# Dashboard_rev4.net
KiCad netlist of a schematic drawn in EAGLE
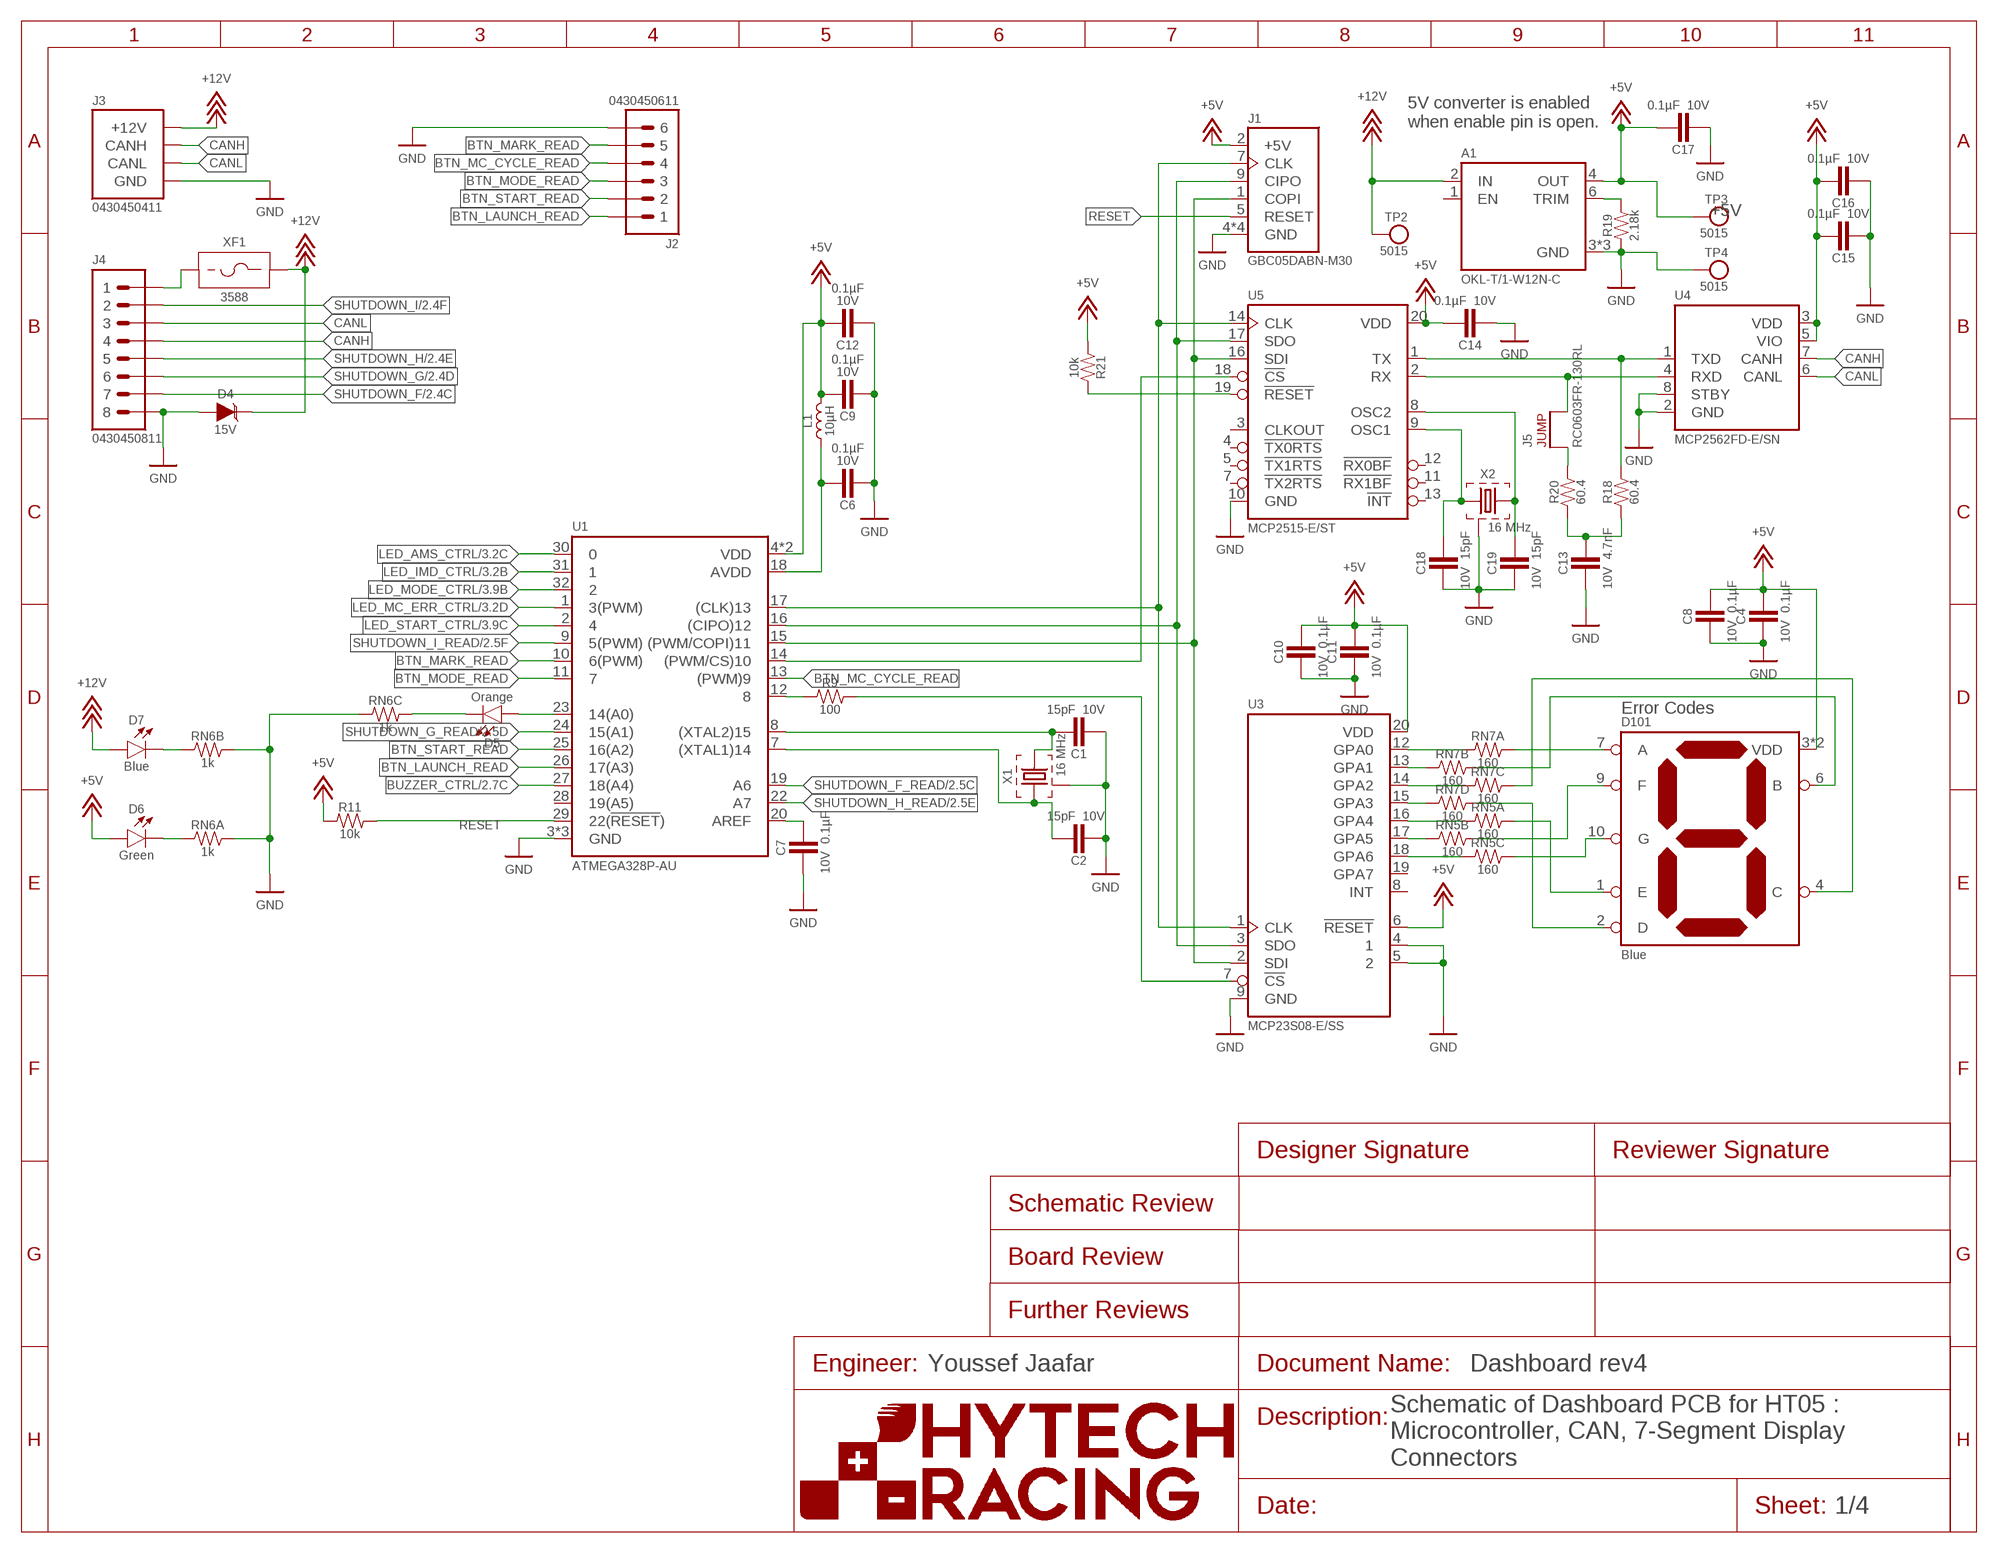
[diagram p0: schematic, sheet 1]
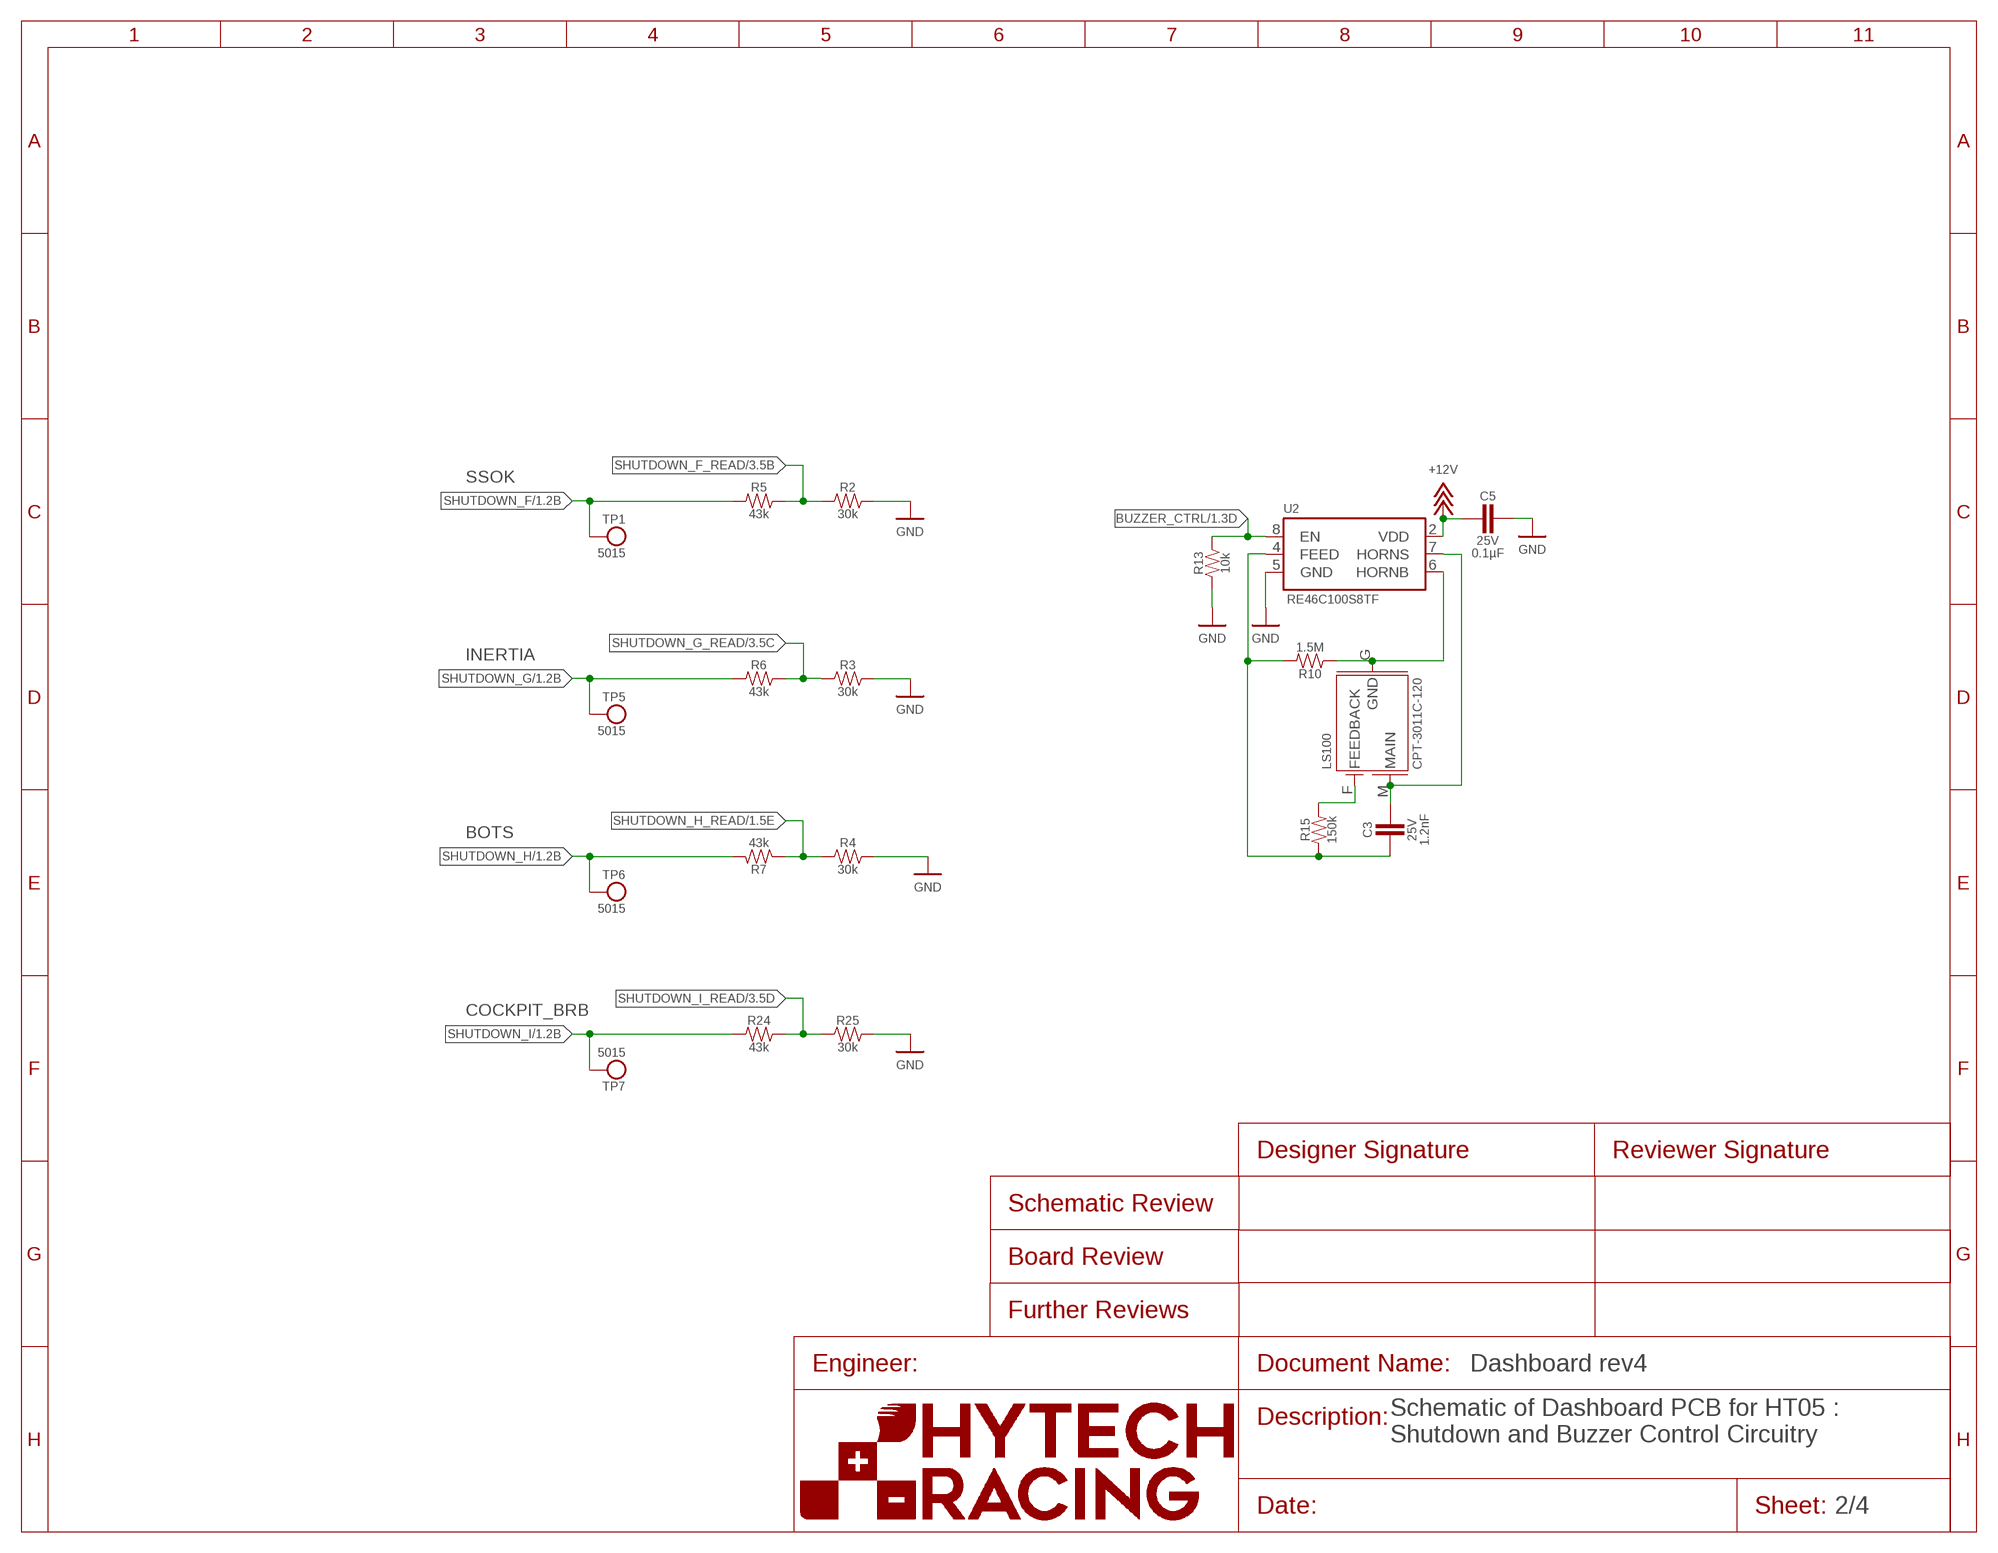
[diagram p1: schematic, sheet 2]
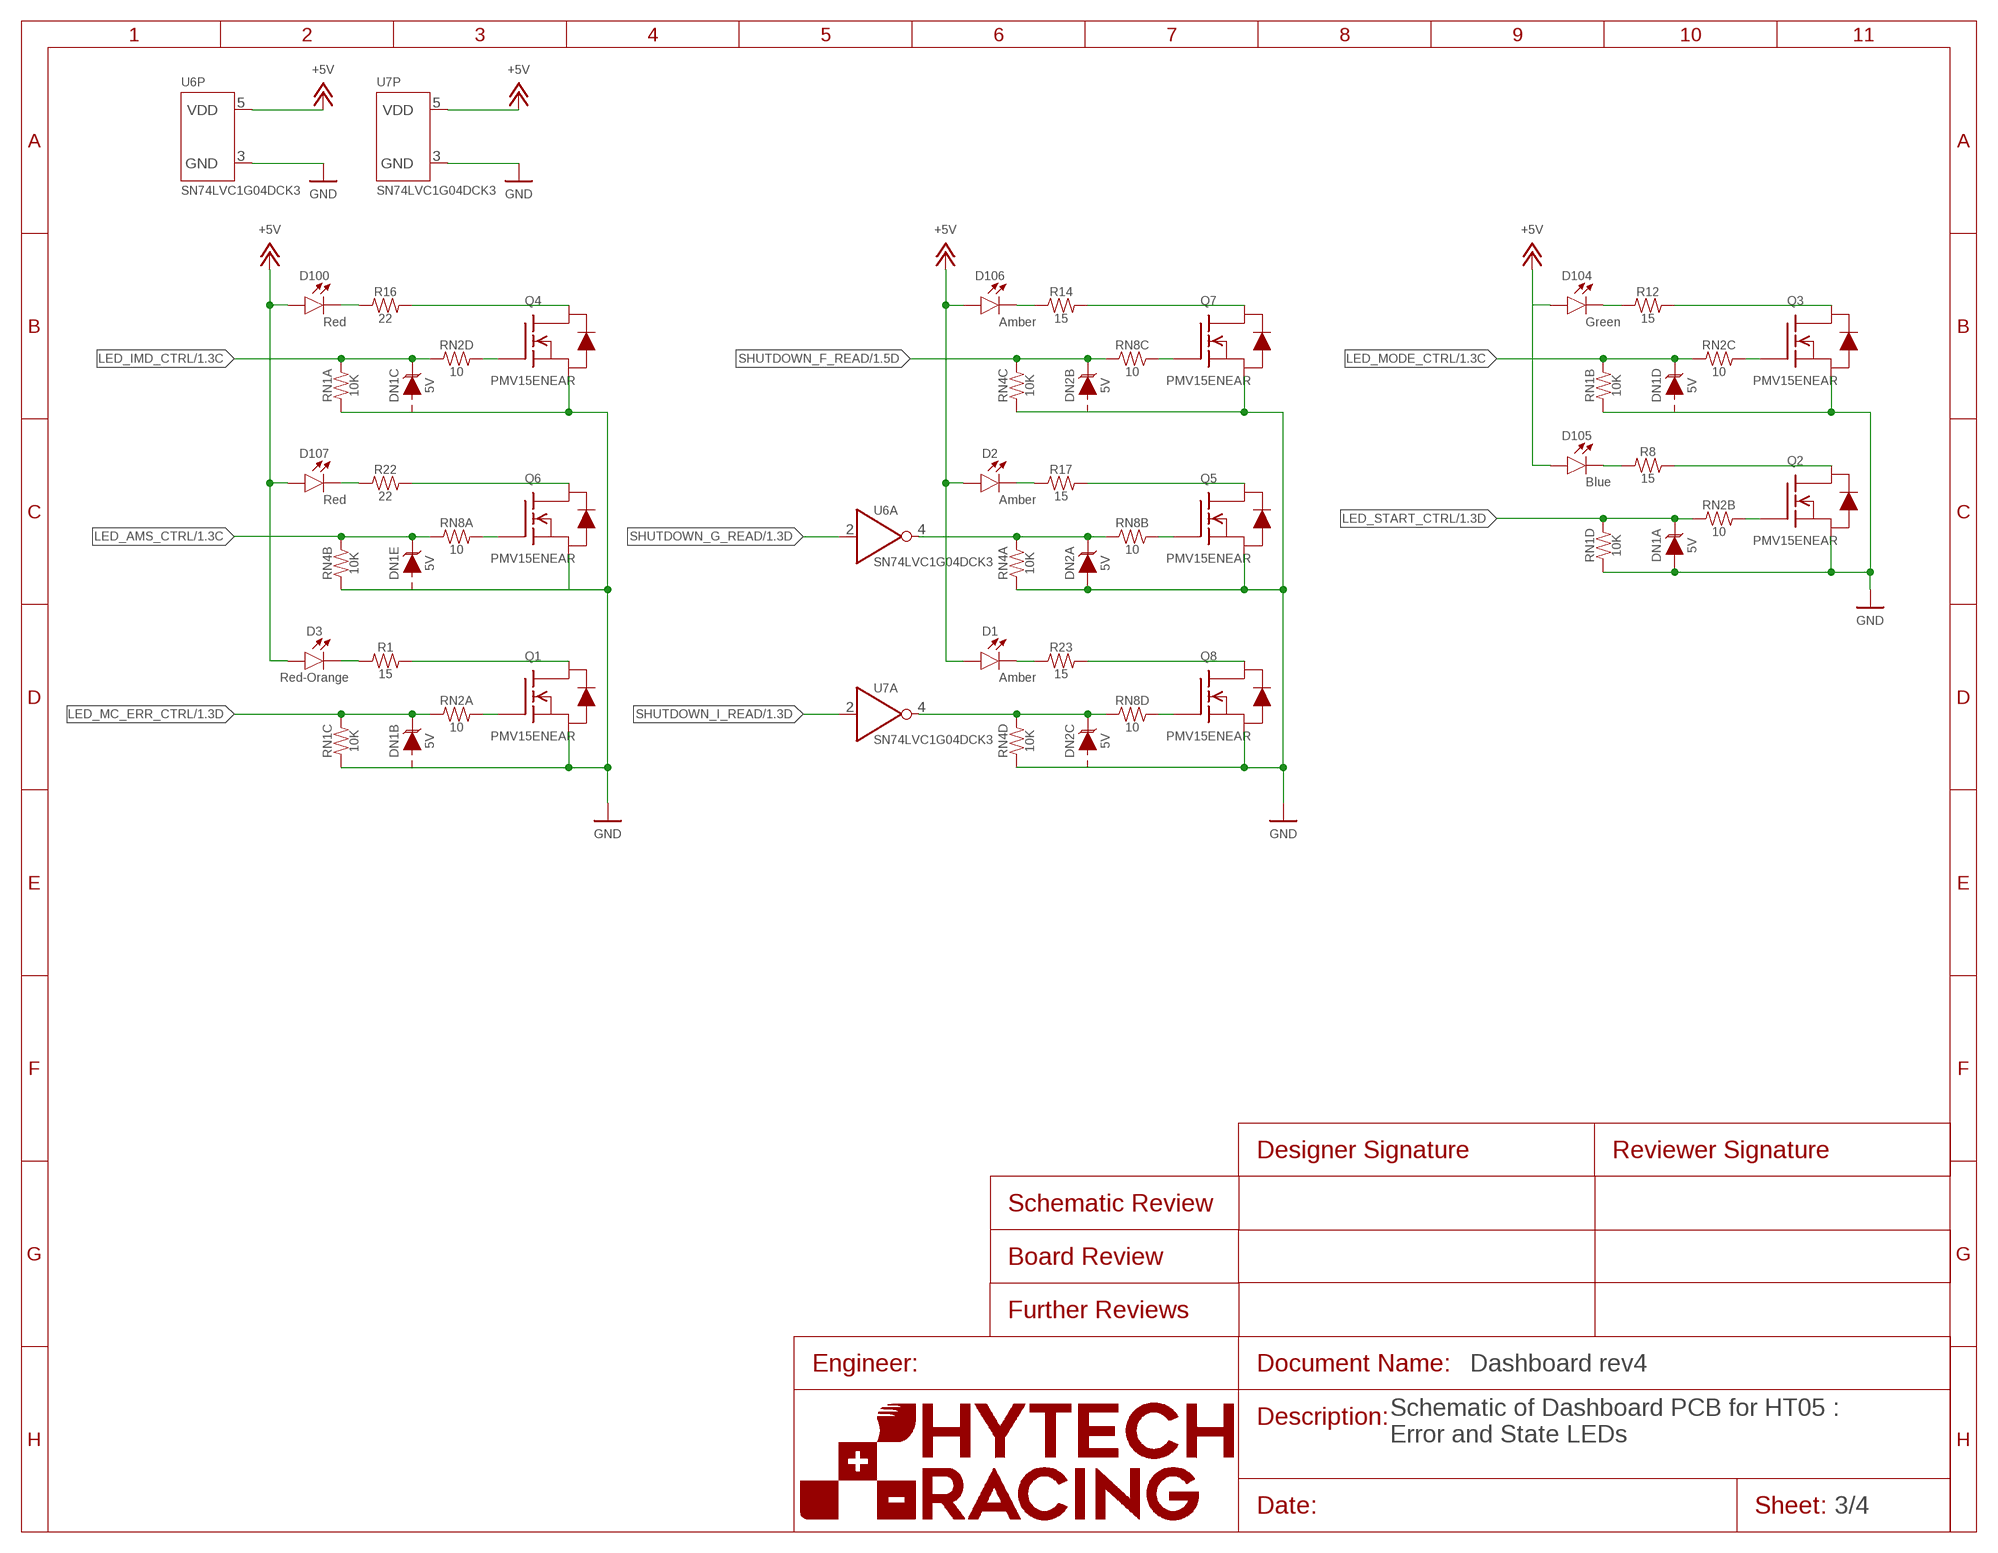
[diagram p2: schematic, sheet 3]
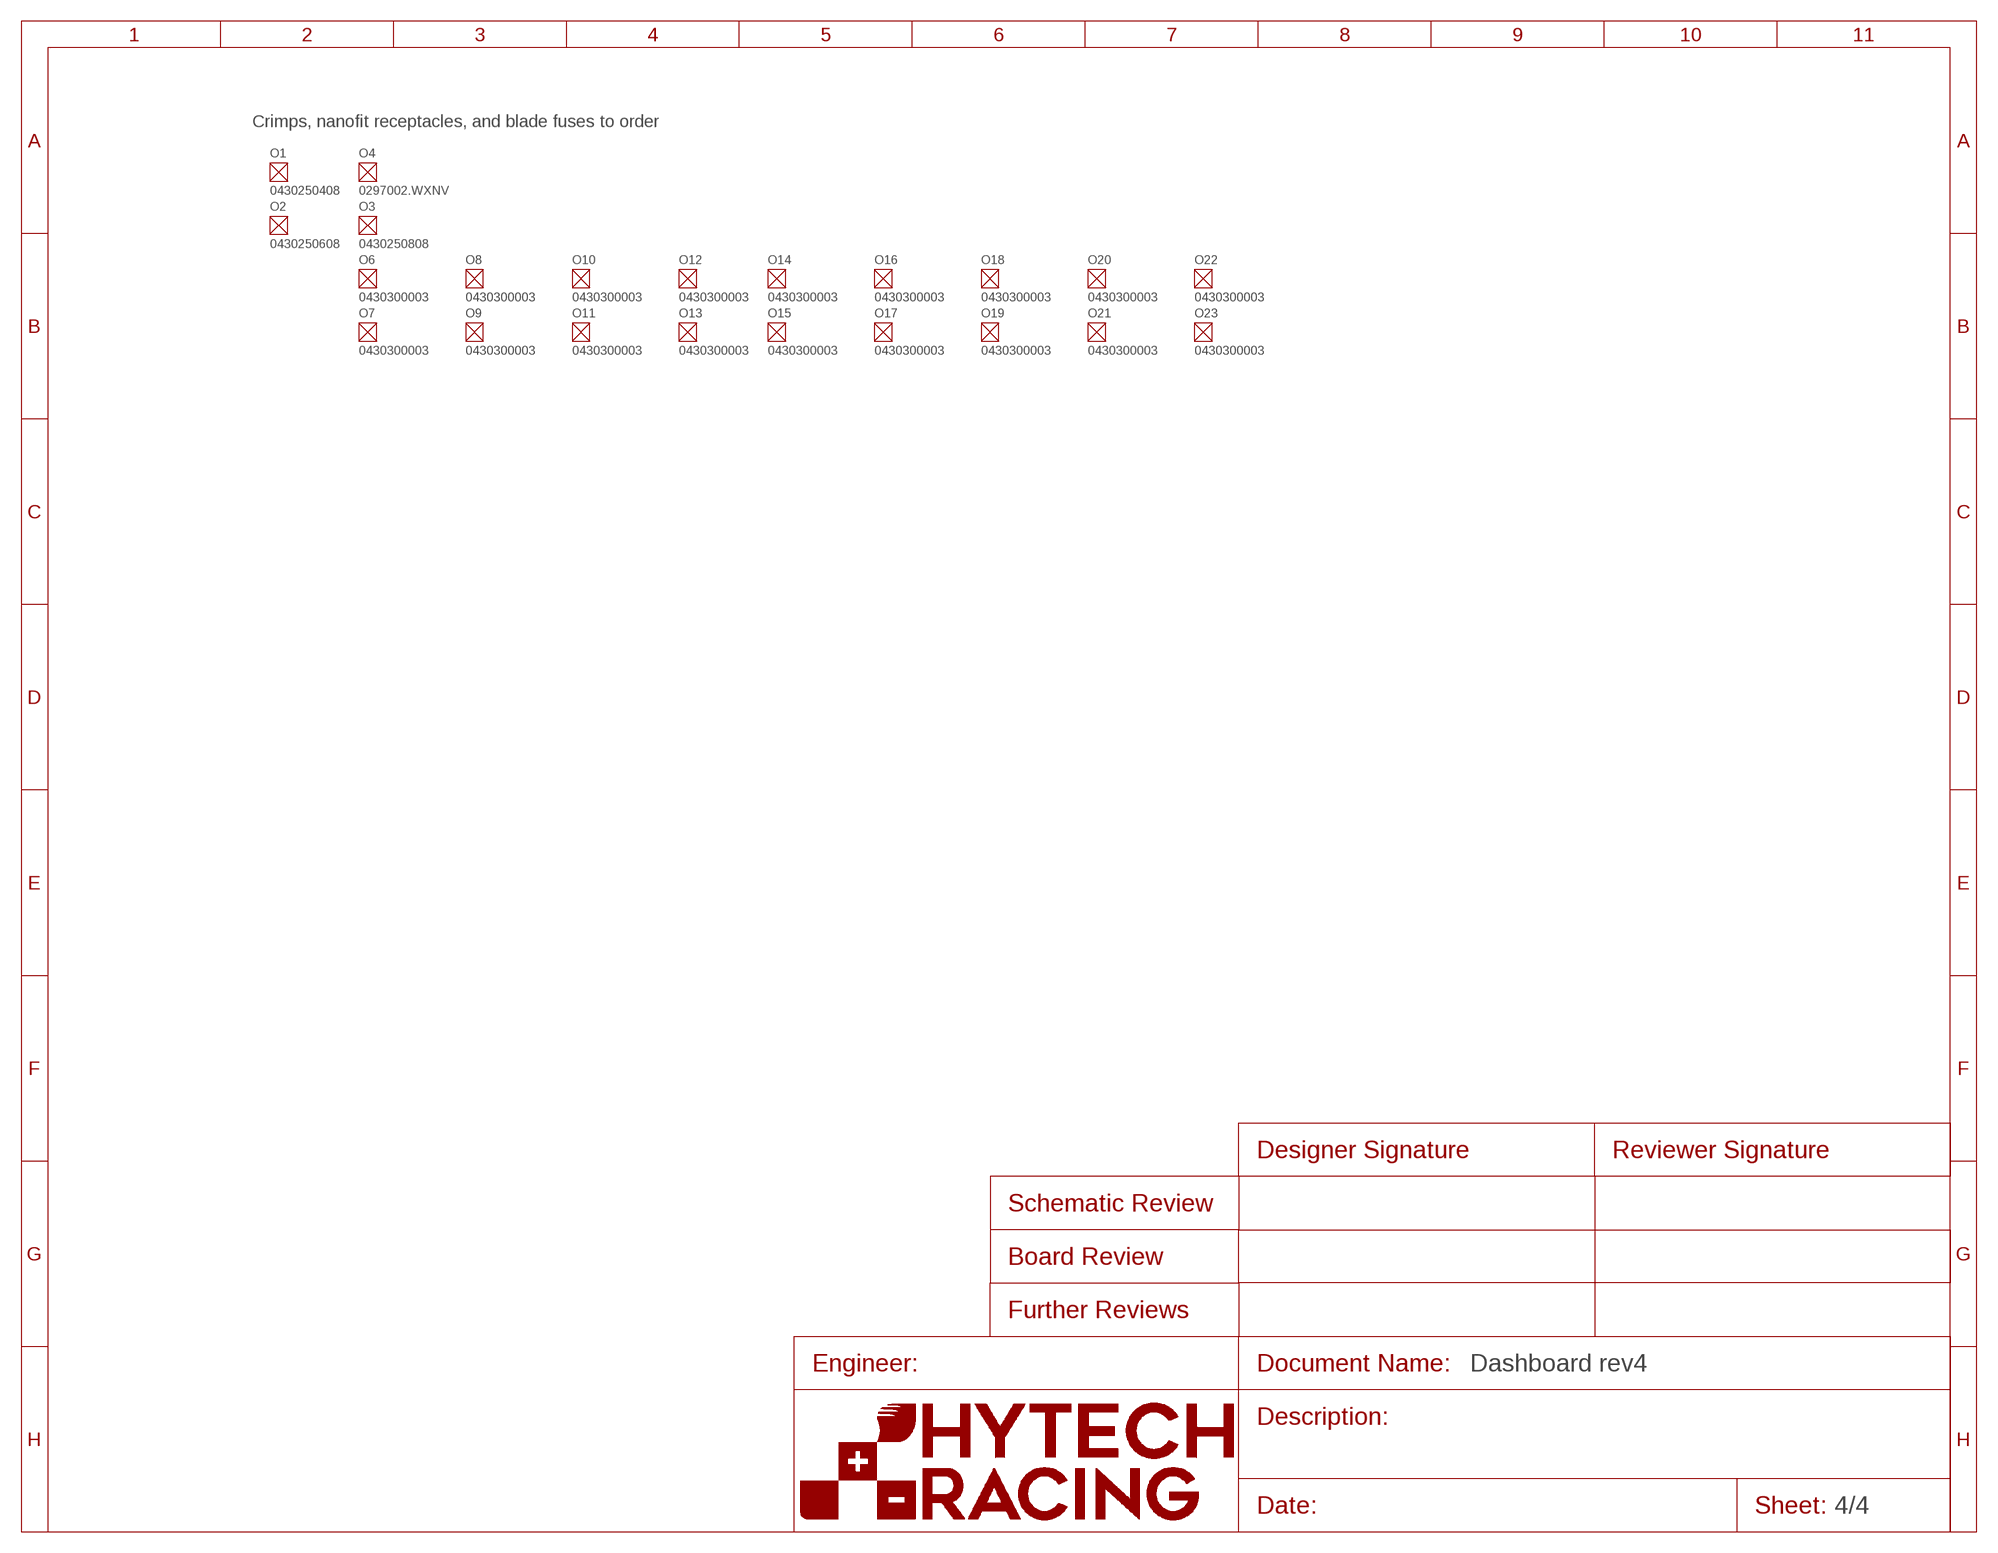
[diagram p3: schematic, sheet 4]

(export (version "E")
  (design (tool "Eeschema 10.0.6"))
  (components
    (comp (ref "C3")
      (value "CAPACITOR_0603_25V_1.2NF")
      (footprint "eagle-import:0603-CAP")
      (fields
        (field (name "CAPACITANCE") "1.2nF")
        (field (name "MANUFACTURER") "YAGEO")
        (field (name "MPN") "CC0603KRX7R8BB122")
        (field (name "TOLERANCE") "10%")
        (field (name "VOLTAGE") "25V")
      )
      (libsource (lib "eagle-import") (part "CAPACITOR_?_060325V_1.2NF"))
    )
    (comp (ref "C5")
      (value "CAPACITOR_0603_25V_0.1UF")
      (footprint "eagle-import:0603-CAP")
      (fields
        (field (name "CAPACITANCE") "0.1µF")
        (field (name "MANUFACTURER") "Samsung Electro-Mechanics")
        (field (name "MPN") "CL10B104KA8NNNC")
        (field (name "TOLERANCE") "10%")
        (field (name "VOLTAGE") "25V")
      )
      (libsource (lib "eagle-import") (part "CAPACITOR_?_060325V_0.1UF"))
    )
    (comp (ref "LS100")
      (value "BUZZER_3_PIN_CPT-3011C-120")
      (footprint "eagle-import:CPT-3011C-120")
      (fields
        (field (name "MANUFACTURER") "CUI Devices")
        (field (name "MPN") "CPT-3011C-120")
        (field (name "VOLTAGE") "12V")
      )
      (libsource (lib "eagle-import") (part "BUZZER_3_PIN_CPT-3011C-120"))
    )
    (comp (ref "R2")
      (value "RESISTOR_0603_30K")
      (footprint "eagle-import:0603-RES")
      (fields
        (field (name "MANUFACTURER") "Panasonic Electronic Components")
        (field (name "MPN") "ERA-3ARB303V")
        (field (name "POWER") "0.1W")
        (field (name "RESISTANCE") "30k")
      )
      (libsource (lib "eagle-import") (part "RESISTOR_?_060330K"))
    )
    (comp (ref "R3")
      (value "RESISTOR_0603_30K")
      (footprint "eagle-import:0603-RES")
      (fields
        (field (name "MANUFACTURER") "Panasonic Electronic Components")
        (field (name "MPN") "ERA-3ARB303V")
        (field (name "POWER") "0.1W")
        (field (name "RESISTANCE") "30k")
      )
      (libsource (lib "eagle-import") (part "RESISTOR_?_060330K"))
    )
    (comp (ref "R4")
      (value "RESISTOR_0603_30K")
      (footprint "eagle-import:0603-RES")
      (fields
        (field (name "MANUFACTURER") "Panasonic Electronic Components")
        (field (name "MPN") "ERA-3ARB303V")
        (field (name "POWER") "0.1W")
        (field (name "RESISTANCE") "30k")
      )
      (libsource (lib "eagle-import") (part "RESISTOR_?_060330K"))
    )
    (comp (ref "R5")
      (value "RESISTOR_0603_43K")
      (footprint "eagle-import:0603-RES")
      (fields
        (field (name "MANUFACTURER") "Yageo")
        (field (name "MPN") "RC0603FR-0743KL")
        (field (name "POWER") "0.1W")
        (field (name "RESISTANCE") "43k")
      )
      (libsource (lib "eagle-import") (part "RESISTOR_?_060343K"))
    )
    (comp (ref "R6")
      (value "RESISTOR_0603_43K")
      (footprint "eagle-import:0603-RES")
      (fields
        (field (name "MANUFACTURER") "Yageo")
        (field (name "MPN") "RC0603FR-0743KL")
        (field (name "POWER") "0.1W")
        (field (name "RESISTANCE") "43k")
      )
      (libsource (lib "eagle-import") (part "RESISTOR_?_060343K"))
    )
    (comp (ref "R7")
      (value "RESISTOR_0603_43K")
      (footprint "eagle-import:0603-RES")
      (fields
        (field (name "MANUFACTURER") "Yageo")
        (field (name "MPN") "RC0603FR-0743KL")
        (field (name "POWER") "0.1W")
        (field (name "RESISTANCE") "43k")
      )
      (libsource (lib "eagle-import") (part "RESISTOR_?_060343K"))
    )
    (comp (ref "R10")
      (value "RESISTOR_0603_1.5M")
      (footprint "eagle-import:0603-RES")
      (fields
        (field (name "MANUFACTURER") "Yageo")
        (field (name "MPN") "RC0603FR-071M5L")
        (field (name "POWER") "0.1W")
        (field (name "RESISTANCE") "1.5M")
      )
      (libsource (lib "eagle-import") (part "RESISTOR_?_06031.5M"))
    )
    (comp (ref "R13")
      (value "RESISTOR_0603_10K")
      (footprint "eagle-import:0603-RES")
      (fields
        (field (name "MANUFACTURER") "Yageo")
        (field (name "MPN") "RC0603FR-0710KL")
        (field (name "POWER") "0.1W")
        (field (name "RESISTANCE") "10k")
      )
      (libsource (lib "eagle-import") (part "RESISTOR_?_060310K"))
    )
    (comp (ref "R15")
      (value "RESISTOR_0603_150K")
      (footprint "eagle-import:0603-RES")
      (fields
        (field (name "MANUFACTURER") "Panasonic Electronic Components")
        (field (name "MPN") "ERA-3AEB154V")
        (field (name "POWER") "0.1W")
        (field (name "RESISTANCE") "150k")
      )
      (libsource (lib "eagle-import") (part "RESISTOR_?_0603150K"))
    )
    (comp (ref "R24")
      (value "RESISTOR_0603_43K")
      (footprint "eagle-import:0603-RES")
      (fields
        (field (name "MANUFACTURER") "Yageo")
        (field (name "MPN") "RC0603FR-0743KL")
        (field (name "POWER") "0.1W")
        (field (name "RESISTANCE") "43k")
      )
      (libsource (lib "eagle-import") (part "RESISTOR_?_060343K"))
    )
    (comp (ref "R25")
      (value "RESISTOR_0603_30K")
      (footprint "eagle-import:0603-RES")
      (fields
        (field (name "MANUFACTURER") "Panasonic Electronic Components")
        (field (name "MPN") "ERA-3ARB303V")
        (field (name "POWER") "0.1W")
        (field (name "RESISTANCE") "30k")
      )
      (libsource (lib "eagle-import") (part "RESISTOR_?_060330K"))
    )
    (comp (ref "TP1")
      (value "TEST_POINT")
      (footprint "eagle-import:5015")
      (fields (field (name "MPN") "5015") (field (name "MANUFACTURER") "Keystone Electronics"))
      (libsource (lib "eagle-import") (part "TEST_POINT"))
    )
    (comp (ref "TP5")
      (value "TEST_POINT")
      (footprint "eagle-import:5015")
      (fields (field (name "MPN") "5015") (field (name "MANUFACTURER") "Keystone Electronics"))
      (libsource (lib "eagle-import") (part "TEST_POINT"))
    )
    (comp (ref "TP6")
      (value "TEST_POINT")
      (footprint "eagle-import:5015")
      (fields (field (name "MPN") "5015") (field (name "MANUFACTURER") "Keystone Electronics"))
      (libsource (lib "eagle-import") (part "TEST_POINT"))
    )
    (comp (ref "TP7")
      (value "TEST_POINT")
      (footprint "eagle-import:5015")
      (fields (field (name "MPN") "5015") (field (name "MANUFACTURER") "Keystone Electronics"))
      (libsource (lib "eagle-import") (part "TEST_POINT"))
    )
    (comp (ref "U2")
      (value "RE46C100")
      (footprint "eagle-import:SOIC-08(NARROW,0.15_)")
      (fields (field (name "MPN") " RE46C100S8TF") (field (name "MANUFACTURER") "Microchip Technology"))
      (libsource (lib "eagle-import") (part "RE46C100"))
    )
    (comp (ref "D1")
      (value "LED_2835_AMBER")
      (footprint "eagle-import:2835-LED")
      (fields
        (field (name "COLOR") "Amber")
        (field (name "MANUFACTURER") "Lumileds")
        (field (name "MPN") "L128-PCA1003500000")
      )
      (libsource (lib "eagle-import") (part "LED_?_2835AMBER"))
    )
    (comp (ref "D2")
      (value "LED_2835_AMBER")
      (footprint "eagle-import:2835-LED")
      (fields
        (field (name "COLOR") "Amber")
        (field (name "MANUFACTURER") "Lumileds")
        (field (name "MPN") "L128-PCA1003500000")
      )
      (libsource (lib "eagle-import") (part "LED_?_2835AMBER"))
    )
    (comp (ref "D3")
      (value "LED_2835_RED-ORANGE")
      (footprint "eagle-import:2835-LED")
      (fields
        (field (name "COLOR") "Red-Orange")
        (field (name "MANUFACTURER") "Lumileds")
        (field (name "MPN") "L128-RNG1003500000 ")
      )
      (libsource (lib "eagle-import") (part "LED_?_2835RED-ORANGE"))
    )
    (comp (ref "D100")
      (value "LED_2835_RED")
      (footprint "eagle-import:2835-LED")
      (fields
        (field (name "COLOR") "Red")
        (field (name "MANUFACTURER") "Lumileds")
        (field (name "MPN") "L128-RED1003500000")
      )
      (libsource (lib "eagle-import") (part "LED_?_2835RED"))
    )
    (comp (ref "D104")
      (value "LED_2835_GREEN")
      (footprint "eagle-import:2835-LED")
      (fields
        (field (name "COLOR") "Green")
        (field (name "MANUFACTURER") "Lumileds")
        (field (name "MPN") "L128-GRN1003500000")
      )
      (libsource (lib "eagle-import") (part "LED_?_2835GREEN"))
    )
    (comp (ref "D105")
      (value "LED_2835_BLUE")
      (footprint "eagle-import:2835-LED")
      (fields
        (field (name "COLOR") "Blue")
        (field (name "MANUFACTURER") "Lumileds")
        (field (name "MPN") "L128-BLU1003500000")
      )
      (libsource (lib "eagle-import") (part "LED_?_2835BLUE"))
    )
    (comp (ref "D106")
      (value "LED_2835_AMBER")
      (footprint "eagle-import:2835-LED")
      (fields
        (field (name "COLOR") "Amber")
        (field (name "MANUFACTURER") "Lumileds")
        (field (name "MPN") "L128-PCA1003500000")
      )
      (libsource (lib "eagle-import") (part "LED_?_2835AMBER"))
    )
    (comp (ref "D107")
      (value "LED_2835_RED")
      (footprint "eagle-import:2835-LED")
      (fields
        (field (name "COLOR") "Red")
        (field (name "MANUFACTURER") "Lumileds")
        (field (name "MPN") "L128-RED1003500000")
      )
      (libsource (lib "eagle-import") (part "LED_?_2835RED"))
    )
    (comp (ref "DN1")
      (value "TVS_ARRAY_5V")
      (footprint "eagle-import:SOT-363")
      (fields
        (field (name "MANUFACTURER") "Vishay General Semiconductor - Diodes Division")
        (field (name "MPN") "VESD05A5-06G-G3-08")
        (field (name "VOLTAGE") "5V")
      )
      (libsource (lib "eagle-import") (part "TVS_ARRAY_5V"))
    )
    (comp (ref "DN2")
      (value "TVS_ARRAY_5V")
      (footprint "eagle-import:SOT-363")
      (fields
        (field (name "MANUFACTURER") "Vishay General Semiconductor - Diodes Division")
        (field (name "MPN") "VESD05A5-06G-G3-08")
        (field (name "VOLTAGE") "5V")
      )
      (libsource (lib "eagle-import") (part "TVS_ARRAY_5V"))
    )
    (comp (ref "Q1")
      (value "TRANSISTOR_N_MOS__PMV15ENEA")
      (footprint "eagle-import:SOT-23")
      (fields (field (name "MANUFACTURER") "Nexperia USA Inc.") (field (name "MPN") "PMV15ENEAR"))
      (libsource (lib "eagle-import") (part "TRANSISTOR_N_MOS_?_PMV15ENEA"))
    )
    (comp (ref "Q2")
      (value "TRANSISTOR_N_MOS__PMV15ENEA")
      (footprint "eagle-import:SOT-23")
      (fields (field (name "MANUFACTURER") "Nexperia USA Inc.") (field (name "MPN") "PMV15ENEAR"))
      (libsource (lib "eagle-import") (part "TRANSISTOR_N_MOS_?_PMV15ENEA"))
    )
    (comp (ref "Q3")
      (value "TRANSISTOR_N_MOS__PMV15ENEA")
      (footprint "eagle-import:SOT-23")
      (fields (field (name "MANUFACTURER") "Nexperia USA Inc.") (field (name "MPN") "PMV15ENEAR"))
      (libsource (lib "eagle-import") (part "TRANSISTOR_N_MOS_?_PMV15ENEA"))
    )
    (comp (ref "Q4")
      (value "TRANSISTOR_N_MOS__PMV15ENEA")
      (footprint "eagle-import:SOT-23")
      (fields (field (name "MANUFACTURER") "Nexperia USA Inc.") (field (name "MPN") "PMV15ENEAR"))
      (libsource (lib "eagle-import") (part "TRANSISTOR_N_MOS_?_PMV15ENEA"))
    )
    (comp (ref "Q5")
      (value "TRANSISTOR_N_MOS__PMV15ENEA")
      (footprint "eagle-import:SOT-23")
      (fields (field (name "MANUFACTURER") "Nexperia USA Inc.") (field (name "MPN") "PMV15ENEAR"))
      (libsource (lib "eagle-import") (part "TRANSISTOR_N_MOS_?_PMV15ENEA"))
    )
    (comp (ref "Q6")
      (value "TRANSISTOR_N_MOS__PMV15ENEA")
      (footprint "eagle-import:SOT-23")
      (fields (field (name "MANUFACTURER") "Nexperia USA Inc.") (field (name "MPN") "PMV15ENEAR"))
      (libsource (lib "eagle-import") (part "TRANSISTOR_N_MOS_?_PMV15ENEA"))
    )
    (comp (ref "Q7")
      (value "TRANSISTOR_N_MOS__PMV15ENEA")
      (footprint "eagle-import:SOT-23")
      (fields (field (name "MANUFACTURER") "Nexperia USA Inc.") (field (name "MPN") "PMV15ENEAR"))
      (libsource (lib "eagle-import") (part "TRANSISTOR_N_MOS_?_PMV15ENEA"))
    )
    (comp (ref "Q8")
      (value "TRANSISTOR_N_MOS__PMV15ENEA")
      (footprint "eagle-import:SOT-23")
      (fields (field (name "MANUFACTURER") "Nexperia USA Inc.") (field (name "MPN") "PMV15ENEAR"))
      (libsource (lib "eagle-import") (part "TRANSISTOR_N_MOS_?_PMV15ENEA"))
    )
    (comp (ref "R1")
      (value "RESISTOR_0603_15")
      (footprint "eagle-import:0603-RES")
      (fields
        (field (name "MANUFACTURER") "Vishay Dale")
        (field (name "MPN") "CRCW060315R0FKEAHP")
        (field (name "POWER") "0.33W")
        (field (name "RESISTANCE") "15")
      )
      (libsource (lib "eagle-import") (part "RESISTOR_?_060315"))
    )
    (comp (ref "R8")
      (value "RESISTOR_0603_15")
      (footprint "eagle-import:0603-RES")
      (fields
        (field (name "MANUFACTURER") "Vishay Dale")
        (field (name "MPN") "CRCW060315R0FKEAHP")
        (field (name "POWER") "0.33W")
        (field (name "RESISTANCE") "15")
      )
      (libsource (lib "eagle-import") (part "RESISTOR_?_060315"))
    )
    (comp (ref "R12")
      (value "RESISTOR_0603_15")
      (footprint "eagle-import:0603-RES")
      (fields
        (field (name "MANUFACTURER") "Vishay Dale")
        (field (name "MPN") "CRCW060315R0FKEAHP")
        (field (name "POWER") "0.33W")
        (field (name "RESISTANCE") "15")
      )
      (libsource (lib "eagle-import") (part "RESISTOR_?_060315"))
    )
    (comp (ref "R14")
      (value "RESISTOR_0603_15")
      (footprint "eagle-import:0603-RES")
      (fields
        (field (name "MANUFACTURER") "Vishay Dale")
        (field (name "MPN") "CRCW060315R0FKEAHP")
        (field (name "POWER") "0.33W")
        (field (name "RESISTANCE") "15")
      )
      (libsource (lib "eagle-import") (part "RESISTOR_?_060315"))
    )
    (comp (ref "R16")
      (value "RESISTOR_0805_22")
      (footprint "eagle-import:0805-RES")
      (fields
        (field (name "MANUFACTURER") "Panasonic Electronic Components")
        (field (name "MPN") "ERJ-P06F22R0V")
        (field (name "POWER") "0.5W")
        (field (name "RESISTANCE") "22")
      )
      (libsource (lib "eagle-import") (part "RESISTOR_?_080522"))
    )
    (comp (ref "R17")
      (value "RESISTOR_0603_15")
      (footprint "eagle-import:0603-RES")
      (fields
        (field (name "MANUFACTURER") "Vishay Dale")
        (field (name "MPN") "CRCW060315R0FKEAHP")
        (field (name "POWER") "0.33W")
        (field (name "RESISTANCE") "15")
      )
      (libsource (lib "eagle-import") (part "RESISTOR_?_060315"))
    )
    (comp (ref "R22")
      (value "RESISTOR_0805_22")
      (footprint "eagle-import:0805-RES")
      (fields
        (field (name "MANUFACTURER") "Panasonic Electronic Components")
        (field (name "MPN") "ERJ-P06F22R0V")
        (field (name "POWER") "0.5W")
        (field (name "RESISTANCE") "22")
      )
      (libsource (lib "eagle-import") (part "RESISTOR_?_080522"))
    )
    (comp (ref "R23")
      (value "RESISTOR_0603_15")
      (footprint "eagle-import:0603-RES")
      (fields
        (field (name "MANUFACTURER") "Vishay Dale")
        (field (name "MPN") "CRCW060315R0FKEAHP")
        (field (name "POWER") "0.33W")
        (field (name "RESISTANCE") "15")
      )
      (libsource (lib "eagle-import") (part "RESISTOR_?_060315"))
    )
    (comp (ref "RN1")
      (value "RESISTOR_NETWORK_4_10K")
      (footprint "eagle-import:1206-RES-ARRAY")
      (fields
        (field (name "MANUFACTURER") "Yageo")
        (field (name "MPN") "TC164-FR-0710KL")
        (field (name "POWER") "1/16W")
        (field (name "RESISTANCE") "10K")
      )
      (libsource (lib "eagle-import") (part "RESISTOR_NETWORK_4_10K"))
    )
    (comp (ref "RN2")
      (value "RESISTOR_NETWORK_4_10")
      (footprint "eagle-import:1206-RES-ARRAY")
      (fields
        (field (name "MANUFACTURER") "Bourns Inc.")
        (field (name "MPN") "CAT16-100J4LF")
        (field (name "POWER") "1/16W")
        (field (name "RESISTANCE") "10")
      )
      (libsource (lib "eagle-import") (part "RESISTOR_NETWORK_4_10"))
    )
    (comp (ref "RN4")
      (value "RESISTOR_NETWORK_4_10K")
      (footprint "eagle-import:1206-RES-ARRAY")
      (fields
        (field (name "MANUFACTURER") "Yageo")
        (field (name "MPN") "TC164-FR-0710KL")
        (field (name "POWER") "1/16W")
        (field (name "RESISTANCE") "10K")
      )
      (libsource (lib "eagle-import") (part "RESISTOR_NETWORK_4_10K"))
    )
    (comp (ref "RN8")
      (value "RESISTOR_NETWORK_4_10")
      (footprint "eagle-import:1206-RES-ARRAY")
      (fields
        (field (name "MANUFACTURER") "Bourns Inc.")
        (field (name "MPN") "CAT16-100J4LF")
        (field (name "POWER") "1/16W")
        (field (name "RESISTANCE") "10")
      )
      (libsource (lib "eagle-import") (part "RESISTOR_NETWORK_4_10"))
    )
    (comp (ref "U6")
      (value "LOGICGATE_INVERTER_DCK3")
      (footprint "eagle-import:SC-70-5")
      (fields (field (name "MANUFACTURER") "Texas Instruments") (field (name "MPN") "SN74LVC1G04DCK3"))
      (libsource (lib "eagle-import") (part "LOGICGATE_INVERTER_DCK3"))
    )
    (comp (ref "U7")
      (value "LOGICGATE_INVERTER_DCK3")
      (footprint "eagle-import:SC-70-5")
      (fields (field (name "MANUFACTURER") "Texas Instruments") (field (name "MPN") "SN74LVC1G04DCK3"))
      (libsource (lib "eagle-import") (part "LOGICGATE_INVERTER_DCK3"))
    )
    (comp (ref "A1")
      (value "OKL-T/1-W12N-COKL")
      (footprint "eagle-import:OKL-T_1-W12")
      (fields
        (field (name "MANUFACTURER") "Murata Power Solutions Inc.")
        (field (name "MPN") "OKL-T/1-W12N-C")
      )
      (libsource (lib "eagle-import") (part "OKL-OKLT/1-W12N-C"))
    )
    (comp (ref "C1")
      (value "CAPACITOR_0603_10V_15PF")
      (footprint "eagle-import:0603-CAP")
      (fields
        (field (name "CAPACITANCE") "15pF")
        (field (name "MANUFACTURER") "Vishay Vitramon")
        (field (name "MPN") "VJ0603A150FXQPW1BC")
        (field (name "TOLERANCE") "1%")
        (field (name "VOLTAGE") "10V")
      )
      (libsource (lib "eagle-import") (part "CAPACITOR_?_060310V_15PF"))
    )
    (comp (ref "C2")
      (value "CAPACITOR_0603_10V_15PF")
      (footprint "eagle-import:0603-CAP")
      (fields
        (field (name "CAPACITANCE") "15pF")
        (field (name "MANUFACTURER") "Vishay Vitramon")
        (field (name "MPN") "VJ0603A150FXQPW1BC")
        (field (name "TOLERANCE") "1%")
        (field (name "VOLTAGE") "10V")
      )
      (libsource (lib "eagle-import") (part "CAPACITOR_?_060310V_15PF"))
    )
    (comp (ref "C4")
      (value "CAPACITOR_0603_10V_0.1UF")
      (footprint "eagle-import:0603-CAP")
      (fields
        (field (name "CAPACITANCE") "0.1µF")
        (field (name "MANUFACTURER") "Vishay Vitramon")
        (field (name "MPN") "VJ0603Y104JXQPW1BC")
        (field (name "TOLERANCE") "5%")
        (field (name "VOLTAGE") "10V")
      )
      (libsource (lib "eagle-import") (part "CAPACITOR_?_060310V_0.1UF"))
    )
    (comp (ref "C6")
      (value "CAPACITOR_0603_10V_0.1UF")
      (footprint "eagle-import:0603-CAP")
      (fields
        (field (name "CAPACITANCE") "0.1µF")
        (field (name "MANUFACTURER") "Vishay Vitramon")
        (field (name "MPN") "VJ0603Y104JXQPW1BC")
        (field (name "TOLERANCE") "5%")
        (field (name "VOLTAGE") "10V")
      )
      (libsource (lib "eagle-import") (part "CAPACITOR_?_060310V_0.1UF"))
    )
    (comp (ref "C7")
      (value "CAPACITOR_0603_10V_0.1UF")
      (footprint "eagle-import:0603-CAP")
      (fields
        (field (name "CAPACITANCE") "0.1µF")
        (field (name "MANUFACTURER") "Vishay Vitramon")
        (field (name "MPN") "VJ0603Y104JXQPW1BC")
        (field (name "TOLERANCE") "5%")
        (field (name "VOLTAGE") "10V")
      )
      (libsource (lib "eagle-import") (part "CAPACITOR_?_060310V_0.1UF"))
    )
    (comp (ref "C8")
      (value "CAPACITOR_0603_10V_0.1UF")
      (footprint "eagle-import:0603-CAP")
      (fields
        (field (name "CAPACITANCE") "0.1µF")
        (field (name "MANUFACTURER") "Vishay Vitramon")
        (field (name "MPN") "VJ0603Y104JXQPW1BC")
        (field (name "TOLERANCE") "5%")
        (field (name "VOLTAGE") "10V")
      )
      (libsource (lib "eagle-import") (part "CAPACITOR_?_060310V_0.1UF"))
    )
    (comp (ref "C9")
      (value "CAPACITOR_0603_10V_0.1UF")
      (footprint "eagle-import:0603-CAP")
      (fields
        (field (name "CAPACITANCE") "0.1µF")
        (field (name "MANUFACTURER") "Vishay Vitramon")
        (field (name "MPN") "VJ0603Y104JXQPW1BC")
        (field (name "TOLERANCE") "5%")
        (field (name "VOLTAGE") "10V")
      )
      (libsource (lib "eagle-import") (part "CAPACITOR_?_060310V_0.1UF"))
    )
    (comp (ref "C10")
      (value "CAPACITOR_0603_10V_0.1UF")
      (footprint "eagle-import:0603-CAP")
      (fields
        (field (name "CAPACITANCE") "0.1µF")
        (field (name "MANUFACTURER") "Vishay Vitramon")
        (field (name "MPN") "VJ0603Y104JXQPW1BC")
        (field (name "TOLERANCE") "5%")
        (field (name "VOLTAGE") "10V")
      )
      (libsource (lib "eagle-import") (part "CAPACITOR_?_060310V_0.1UF"))
    )
    (comp (ref "C11")
      (value "CAPACITOR_0603_10V_0.1UF")
      (footprint "eagle-import:0603-CAP")
      (fields
        (field (name "CAPACITANCE") "0.1µF")
        (field (name "MANUFACTURER") "Vishay Vitramon")
        (field (name "MPN") "VJ0603Y104JXQPW1BC")
        (field (name "TOLERANCE") "5%")
        (field (name "VOLTAGE") "10V")
      )
      (libsource (lib "eagle-import") (part "CAPACITOR_?_060310V_0.1UF"))
    )
    (comp (ref "C12")
      (value "CAPACITOR_0603_10V_0.1UF")
      (footprint "eagle-import:0603-CAP")
      (fields
        (field (name "CAPACITANCE") "0.1µF")
        (field (name "MANUFACTURER") "Vishay Vitramon")
        (field (name "MPN") "VJ0603Y104JXQPW1BC")
        (field (name "TOLERANCE") "5%")
        (field (name "VOLTAGE") "10V")
      )
      (libsource (lib "eagle-import") (part "CAPACITOR_?_060310V_0.1UF"))
    )
    (comp (ref "C13")
      (value "CAPACITOR_0603_10V_4.7NF")
      (footprint "eagle-import:0603-CAP")
      (fields
        (field (name "CAPACITANCE") "4.7nF")
        (field (name "MANUFACTURER") "Würth Elektronik")
        (field (name "MPN") "885012206012")
        (field (name "TOLERANCE") "10%")
        (field (name "VOLTAGE") "10V")
      )
      (libsource (lib "eagle-import") (part "CAPACITOR_?_060310V_4.7NF"))
    )
    (comp (ref "C14")
      (value "CAPACITOR_0603_10V_0.1UF")
      (footprint "eagle-import:0603-CAP")
      (fields
        (field (name "CAPACITANCE") "0.1µF")
        (field (name "MANUFACTURER") "Vishay Vitramon")
        (field (name "MPN") "VJ0603Y104JXQPW1BC")
        (field (name "TOLERANCE") "5%")
        (field (name "VOLTAGE") "10V")
      )
      (libsource (lib "eagle-import") (part "CAPACITOR_?_060310V_0.1UF"))
    )
    (comp (ref "C15")
      (value "CAPACITOR_0603_10V_0.1UF")
      (footprint "eagle-import:0603-CAP")
      (fields
        (field (name "CAPACITANCE") "0.1µF")
        (field (name "MANUFACTURER") "Vishay Vitramon")
        (field (name "MPN") "VJ0603Y104JXQPW1BC")
        (field (name "TOLERANCE") "5%")
        (field (name "VOLTAGE") "10V")
      )
      (libsource (lib "eagle-import") (part "CAPACITOR_?_060310V_0.1UF"))
    )
    (comp (ref "C16")
      (value "CAPACITOR_0603_10V_0.1UF")
      (footprint "eagle-import:0603-CAP")
      (fields
        (field (name "CAPACITANCE") "0.1µF")
        (field (name "MANUFACTURER") "Vishay Vitramon")
        (field (name "MPN") "VJ0603Y104JXQPW1BC")
        (field (name "TOLERANCE") "5%")
        (field (name "VOLTAGE") "10V")
      )
      (libsource (lib "eagle-import") (part "CAPACITOR_?_060310V_0.1UF"))
    )
    (comp (ref "C17")
      (value "CAPACITOR_0603_10V_0.1UF")
      (footprint "eagle-import:0603-CAP")
      (fields
        (field (name "CAPACITANCE") "0.1µF")
        (field (name "MANUFACTURER") "Vishay Vitramon")
        (field (name "MPN") "VJ0603Y104JXQPW1BC")
        (field (name "TOLERANCE") "5%")
        (field (name "VOLTAGE") "10V")
      )
      (libsource (lib "eagle-import") (part "CAPACITOR_?_060310V_0.1UF"))
    )
    (comp (ref "C18")
      (value "CAPACITOR_0603_10V_15PF")
      (footprint "eagle-import:0603-CAP")
      (fields
        (field (name "CAPACITANCE") "15pF")
        (field (name "MANUFACTURER") "Vishay Vitramon")
        (field (name "MPN") "VJ0603A150FXQPW1BC")
        (field (name "TOLERANCE") "1%")
        (field (name "VOLTAGE") "10V")
      )
      (libsource (lib "eagle-import") (part "CAPACITOR_?_060310V_15PF"))
    )
    (comp (ref "C19")
      (value "CAPACITOR_0603_10V_15PF")
      (footprint "eagle-import:0603-CAP")
      (fields
        (field (name "CAPACITANCE") "15pF")
        (field (name "MANUFACTURER") "Vishay Vitramon")
        (field (name "MPN") "VJ0603A150FXQPW1BC")
        (field (name "TOLERANCE") "1%")
        (field (name "VOLTAGE") "10V")
      )
      (libsource (lib "eagle-import") (part "CAPACITOR_?_060310V_15PF"))
    )
    (comp (ref "D4")
      (value "TVS_15V")
      (footprint "eagle-import:SOT-23")
      (fields
        (field (name "MANUFACTURER") "Vishay General Semiconductor - Diodes Division")
        (field (name "MPN") "GSOT15-E3-08")
        (field (name "VOLTAGE") "15V")
      )
      (libsource (lib "eagle-import") (part "TVS_15V"))
    )
    (comp (ref "D5")
      (value "LED_0603_ORANGE")
      (footprint "eagle-import:0603-LED")
      (fields
        (field (name "COLOR") "Orange")
        (field (name "MANUFACTURER") "Kingbright")
        (field (name "MPN") "APT1608SECK")
      )
      (libsource (lib "eagle-import") (part "LED_?_0603ORANGE"))
    )
    (comp (ref "D6")
      (value "LED_0603_GREEN")
      (footprint "eagle-import:0603-LED")
      (fields
        (field (name "COLOR") "Green")
        (field (name "MANUFACTURER") "Kingbright")
        (field (name "MPN") "APT1608ZGCK")
      )
      (libsource (lib "eagle-import") (part "LED_?_0603GREEN"))
    )
    (comp (ref "D7")
      (value "LED_0603_BLUE")
      (footprint "eagle-import:0603-LED")
      (fields
        (field (name "COLOR") "Blue")
        (field (name "MANUFACTURER") "Kingbright")
        (field (name "MPN") "APT1608VBC/D")
      )
      (libsource (lib "eagle-import") (part "LED_?_0603BLUE"))
    )
    (comp (ref "D101")
      (value "LED_7_SEGMENT_BLUE_DSM7TA")
      (footprint "eagle-import:DSM7T")
      (fields
        (field (name "COLOR") "Blue")
        (field (name "MANUFACTURER") "Visual Communications Company")
        (field (name "MPN") "DSM7TA56106T")
      )
      (libsource (lib "eagle-import") (part "LED_7_SEGMENT_DSM7TABLUE_"))
    )
    (comp (ref "J1")
      (value "CONNECTOR-AVR-ISP_2X05_SMD")
      (footprint "eagle-import:2X05_SMD")
      (fields
        (field (name "MPN") "GBC05DABN-M30")
        (field (name "MANUFACTURER") "Sullins Connector Solutions")
      )
      (libsource (lib "eagle-import") (part "CONNECTOR-AVR-ISP_?2X05_SMD"))
    )
    (comp (ref "J2")
      (value "CONNECTOR-6_μF_S_RA_")
      (footprint "eagle-import:MOLEX_MICROFIT_SMD_RIGHTANGLE_06_DUAL")
      (fields (field (name "MPN") "0430450611") (field (name "MANUFACTURER") "Molex"))
      (libsource (lib "eagle-import") (part "CONNECTOR-6_?_μF_S_RA"))
    )
    (comp (ref "J3")
      (value "CONNECTOR-CAN_μF_S_RA_")
      (footprint "eagle-import:MOLEX_MICROFIT_SMD_RIGHTANGLE_04_DUAL")
      (fields (field (name "MPN") "0430450411") (field (name "MANUFACTURER") "Molex"))
      (libsource (lib "eagle-import") (part "CONNECTOR-CAN_?_μF_S_RA"))
    )
    (comp (ref "J4")
      (value "CONNECTOR-8_μF_S_RA_")
      (footprint "eagle-import:MOLEX_MICROFIT_SMD_RIGHTANGLE_08_DUAL")
      (fields (field (name "MPN") "0430450811") (field (name "MANUFACTURER") "Molex"))
      (libsource (lib "eagle-import") (part "CONNECTOR-8_?_μF_S_RA"))
    )
    (comp (ref "J5")
      (value "JUMPER_0603_")
      (footprint "eagle-import:0603-RES")
      (fields (field (name "MPN") "RC0603FR-130RL") (field (name "MANUFACTURER") "YAGEO"))
      (libsource (lib "eagle-import") (part "JUMPER_?_0603"))
    )
    (comp (ref "L1")
      (value "INDUCTOR_LQM18DH100M70_10UH")
      (footprint "eagle-import:0603-IND")
      (fields
        (field (name "INDUCTANCE") "10µH")
        (field (name "MANUFACTURER") "Murata Electronics")
        (field (name "MPN") "LQM18DH100M70L")
        (field (name "TOLERANCE") "20%")
      )
      (libsource (lib "eagle-import") (part "INDUCTOR_?_LQM18DH100M7010UH"))
    )
    (comp (ref "R9")
      (value "RESISTOR_0603_100")
      (footprint "eagle-import:0603-RES")
      (fields
        (field (name "MANUFACTURER") "Yageo")
        (field (name "MPN") "RC0603FR-07100RL")
        (field (name "POWER") "0.1W")
        (field (name "RESISTANCE") "100")
      )
      (libsource (lib "eagle-import") (part "RESISTOR_?_0603100"))
    )
    (comp (ref "R11")
      (value "RESISTOR_0603_10K")
      (footprint "eagle-import:0603-RES")
      (fields
        (field (name "MANUFACTURER") "Yageo")
        (field (name "MPN") "RC0603FR-0710KL")
        (field (name "POWER") "0.1W")
        (field (name "RESISTANCE") "10k")
      )
      (libsource (lib "eagle-import") (part "RESISTOR_?_060310K"))
    )
    (comp (ref "R18")
      (value "RESISTOR_0603_60.4")
      (footprint "eagle-import:0603-RES")
      (fields
        (field (name "MANUFACTURER") "Yageo")
        (field (name "MPN") "RC0603FR-0760R4L")
        (field (name "POWER") "0.1W")
        (field (name "RESISTANCE") "60.4")
      )
      (libsource (lib "eagle-import") (part "RESISTOR_?_060360.4"))
    )
    (comp (ref "R19")
      (value "RESISTOR_0603_2.18K")
      (footprint "eagle-import:0603-RES")
      (fields
        (field (name "MANUFACTURER") "YAGEO")
        (field (name "MPN") "RT0805BRD072K18L")
        (field (name "POWER") "0.125W")
        (field (name "RESISTANCE") "2.18k")
      )
      (libsource (lib "eagle-import") (part "RESISTOR_?_06032.18K"))
    )
    (comp (ref "R20")
      (value "RESISTOR_0603_60.4")
      (footprint "eagle-import:0603-RES")
      (fields
        (field (name "MANUFACTURER") "Yageo")
        (field (name "MPN") "RC0603FR-0760R4L")
        (field (name "POWER") "0.1W")
        (field (name "RESISTANCE") "60.4")
      )
      (libsource (lib "eagle-import") (part "RESISTOR_?_060360.4"))
    )
    (comp (ref "R21")
      (value "RESISTOR_0603_10K")
      (footprint "eagle-import:0603-RES")
      (fields
        (field (name "MANUFACTURER") "Yageo")
        (field (name "MPN") "RC0603FR-0710KL")
        (field (name "POWER") "0.1W")
        (field (name "RESISTANCE") "10k")
      )
      (libsource (lib "eagle-import") (part "RESISTOR_?_060310K"))
    )
    (comp (ref "RN5")
      (value "RESISTOR_NETWORK_4_160")
      (footprint "eagle-import:1206-RES-ARRAY")
      (fields
        (field (name "MANUFACTURER") "Yageo")
        (field (name "MPN") "YC164-JR-07160RL")
        (field (name "POWER") "1/16W")
        (field (name "RESISTANCE") "160")
      )
      (libsource (lib "eagle-import") (part "RESISTOR_NETWORK_4_160"))
    )
    (comp (ref "RN6")
      (value "RESISTOR_NETWORK_4_1K")
      (footprint "eagle-import:1206-RES-ARRAY")
      (fields
        (field (name "MANUFACTURER") "Yageo")
        (field (name "MPN") "YC164-FR-071KL")
        (field (name "POWER") "1/16W")
        (field (name "RESISTANCE") "1k")
      )
      (libsource (lib "eagle-import") (part "RESISTOR_NETWORK_4_1K"))
    )
    (comp (ref "RN7")
      (value "RESISTOR_NETWORK_4_160")
      (footprint "eagle-import:1206-RES-ARRAY")
      (fields
        (field (name "MANUFACTURER") "Yageo")
        (field (name "MPN") "YC164-JR-07160RL")
        (field (name "POWER") "1/16W")
        (field (name "RESISTANCE") "160")
      )
      (libsource (lib "eagle-import") (part "RESISTOR_NETWORK_4_160"))
    )
    (comp (ref "TP2")
      (value "TEST_POINT")
      (footprint "eagle-import:5015")
      (fields (field (name "MPN") "5015") (field (name "MANUFACTURER") "Keystone Electronics"))
      (libsource (lib "eagle-import") (part "TEST_POINT"))
    )
    (comp (ref "TP3")
      (value "TEST_POINT")
      (footprint "eagle-import:5015")
      (fields
        (field (name "MPN") "5015")
        (field (name "MANUFACTURER") "Keystone Electronics")
        (field (name "SIGNAL") "+5V")
      )
      (libsource (lib "eagle-import") (part "TEST_POINT"))
    )
    (comp (ref "TP4")
      (value "TEST_POINT")
      (footprint "eagle-import:5015")
      (fields (field (name "MPN") "5015") (field (name "MANUFACTURER") "Keystone Electronics"))
      (libsource (lib "eagle-import") (part "TEST_POINT"))
    )
    (comp (ref "U1")
      (value "ATMEGA328P-AU")
      (footprint "eagle-import:TQFP-32")
      (fields (field (name "MPN") "ATMEGA328P-AU") (field (name "MANUFACTURER") "Microchip Technology"))
      (libsource (lib "eagle-import") (part "ATMEGA328P-AU"))
    )
    (comp (ref "U3")
      (value "MCP23S08")
      (footprint "eagle-import:SSOP-20")
      (fields (field (name "MPN") "MCP23S08-E/SS") (field (name "MANUFACTURER") "Microchip Technology"))
      (libsource (lib "eagle-import") (part "MCP23S08"))
    )
    (comp (ref "U4")
      (value "MCP2562FD")
      (footprint "eagle-import:SOIC-08(NARROW,0.15_)")
      (fields (field (name "MPN") "MCP2562FD-E/SN") (field (name "MANUFACTURER") "Microchip Technology"))
      (libsource (lib "eagle-import") (part "MCP2562FD"))
    )
    (comp (ref "U5")
      (value "MCP2515")
      (footprint "eagle-import:TSSOP-20")
      (fields (field (name "MPN") "MCP2515-E/ST") (field (name "MANUFACTURER") "Microchip Technology"))
      (libsource (lib "eagle-import") (part "MCP2515"))
    )
    (comp (ref "X1")
      (value "CRYSTAL_16MHZ")
      (footprint "eagle-import:ECX-42")
      (fields
        (field (name "FREQUENCY") "16 MHz")
        (field (name "MANUFACTURER") "TXC CORPORATION")
        (field (name "MPN") "ECS-160-10-42-CKM-TR")
      )
      (libsource (lib "eagle-import") (part "CRYSTAL_16MHZ"))
    )
    (comp (ref "X2")
      (value "CRYSTAL_16MHZ")
      (footprint "eagle-import:ECX-42")
      (fields
        (field (name "FREQUENCY") "16 MHz")
        (field (name "MANUFACTURER") "TXC CORPORATION")
        (field (name "MPN") "ECS-160-10-42-CKM-TR")
      )
      (libsource (lib "eagle-import") (part "CRYSTAL_16MHZ"))
    )
    (comp (ref "XF1")
      (value "FUSE_HOLDER_MINIBLADESMD")
      (footprint "eagle-import:3588")
      (fields (field (name "MANUFACTURER") "Keystone Electronics") (field (name "MPN") "3588"))
      (libsource (lib "eagle-import") (part "FUSE_HOLDER_SMDMINIBLADE"))
    )
  )
  (nets
    (net (code "1") (name "+12V") (class "Default")
      (node (ref "A1") (pin "2") (pinfunction "IN_2") (pintype "input"))
      (node (ref "C5") (pin "2") (pinfunction "2_2") (pintype "passive"))
      (node (ref "D4") (pin "3") (pinfunction "C_3") (pintype "passive"))
      (node (ref "D7") (pin "2") (pinfunction "A_2") (pintype "passive"))
      (node (ref "J3") (pin "1") (pinfunction "+12V_1") (pintype "power_in"))
      (node (ref "TP2") (pin "1") (pinfunction "1_1") (pintype "passive"))
      (node (ref "U2") (pin "2") (pinfunction "VDD_2") (pintype "power_in"))
      (node (ref "XF1") (pin "3") (pinfunction "2_3") (pintype "passive"))
      (node (ref "XF1") (pin "4") (pinfunction "2_4") (pintype "passive"))
    )
    (net (code "2") (name "BTN_LAUNCH_READ") (class "Default")
      (node (ref "J2") (pin "1") (pinfunction "1_1") (pintype "passive"))
      (node (ref "U1") (pin "26") (pinfunction "17(A3)_26") (pintype "bidirectional"))
    )
    (net (code "3") (name "BTN_MARK_READ") (class "Default")
      (node (ref "J2") (pin "5") (pinfunction "5_5") (pintype "passive"))
      (node (ref "U1") (pin "10") (pinfunction "6(PWM)_10") (pintype "bidirectional"))
    )
    (net (code "4") (name "BTN_MC_CYCLE_READ") (class "Default")
      (node (ref "J2") (pin "4") (pinfunction "4_4") (pintype "passive"))
      (node (ref "U1") (pin "13") (pinfunction "(PWM)9_13") (pintype "bidirectional"))
    )
    (net (code "5") (name "BTN_MODE_READ") (class "Default")
      (node (ref "J2") (pin "3") (pinfunction "3_3") (pintype "passive"))
      (node (ref "U1") (pin "11") (pinfunction "7_11") (pintype "bidirectional"))
    )
    (net (code "6") (name "BTN_START_READ") (class "Default")
      (node (ref "J2") (pin "2") (pinfunction "2_2") (pintype "passive"))
      (node (ref "U1") (pin "25") (pinfunction "16(A2)_25") (pintype "bidirectional"))
    )
    (net (code "7") (name "BUZZER_CTRL") (class "Default")
      (node (ref "R13") (pin "2") (pinfunction "2_2") (pintype "passive"))
      (node (ref "U1") (pin "27") (pinfunction "18(A4)_27") (pintype "bidirectional"))
      (node (ref "U2") (pin "8") (pinfunction "EN_8") (pintype "input"))
    )
    (net (code "8") (name "CANH") (class "Default")
      (node (ref "J3") (pin "4") (pinfunction "CANH_4") (pintype "bidirectional"))
      (node (ref "J4") (pin "4") (pinfunction "4_4") (pintype "passive"))
      (node (ref "U4") (pin "7") (pinfunction "CANH_7") (pintype "bidirectional"))
    )
    (net (code "9") (name "CANL") (class "Default")
      (node (ref "J3") (pin "3") (pinfunction "CANL_3") (pintype "bidirectional"))
      (node (ref "J4") (pin "3") (pinfunction "3_3") (pintype "passive"))
      (node (ref "U4") (pin "6") (pinfunction "CANL_6") (pintype "bidirectional"))
    )
    (net (code "10") (name "GND") (class "Default")
      (node (ref "A1") (pin "11") (pinfunction "GND_11") (pintype "power_in"))
      (node (ref "A1") (pin "3") (pinfunction "GND_3") (pintype "power_in"))
      (node (ref "A1") (pin "7") (pinfunction "GND_7") (pintype "power_in"))
      (node (ref "C1") (pin "2") (pinfunction "2_2") (pintype "passive"))
      (node (ref "C10") (pin "2") (pinfunction "2_2") (pintype "passive"))
      (node (ref "C11") (pin "2") (pinfunction "2_2") (pintype "passive"))
      (node (ref "C12") (pin "2") (pinfunction "2_2") (pintype "passive"))
      (node (ref "C13") (pin "2") (pinfunction "2_2") (pintype "passive"))
      (node (ref "C14") (pin "2") (pinfunction "2_2") (pintype "passive"))
      (node (ref "C15") (pin "2") (pinfunction "2_2") (pintype "passive"))
      (node (ref "C16") (pin "2") (pinfunction "2_2") (pintype "passive"))
      (node (ref "C17") (pin "2") (pinfunction "2_2") (pintype "passive"))
      (node (ref "C18") (pin "2") (pinfunction "2_2") (pintype "passive"))
      (node (ref "C19") (pin "2") (pinfunction "2_2") (pintype "passive"))
      (node (ref "C2") (pin "2") (pinfunction "2_2") (pintype "passive"))
      (node (ref "C4") (pin "2") (pinfunction "2_2") (pintype "passive"))
      (node (ref "C5") (pin "1") (pinfunction "1_1") (pintype "passive"))
      (node (ref "C6") (pin "2") (pinfunction "2_2") (pintype "passive"))
      (node (ref "C7") (pin "2") (pinfunction "2_2") (pintype "passive"))
      (node (ref "C8") (pin "2") (pinfunction "2_2") (pintype "passive"))
      (node (ref "C9") (pin "2") (pinfunction "2_2") (pintype "passive"))
      (node (ref "D4") (pin "1") (pinfunction "A_1") (pintype "passive"))
      (node (ref "DN1") (pin "2") (pinfunction "A_2") (pintype "passive"))
      (node (ref "DN2") (pin "2") (pinfunction "A_2") (pintype "passive"))
      (node (ref "J1") (pin "10") (pinfunction "GND_10") (pintype "power_in"))
      (node (ref "J1") (pin "4") (pinfunction "GND_4") (pintype "power_in"))
      (node (ref "J1") (pin "6") (pinfunction "GND_6") (pintype "power_in"))
      (node (ref "J1") (pin "8") (pinfunction "GND_8") (pintype "power_in"))
      (node (ref "J2") (pin "6") (pinfunction "6_6") (pintype "passive"))
      (node (ref "J3") (pin "2") (pinfunction "GND_2") (pintype "power_in"))
      (node (ref "J4") (pin "8") (pinfunction "8_8") (pintype "passive"))
      (node (ref "Q1") (pin "2") (pinfunction "S_2") (pintype "passive"))
      (node (ref "Q2") (pin "2") (pinfunction "S_2") (pintype "passive"))
      (node (ref "Q3") (pin "2") (pinfunction "S_2") (pintype "passive"))
      (node (ref "Q4") (pin "2") (pinfunction "S_2") (pintype "passive"))
      (node (ref "Q5") (pin "2") (pinfunction "S_2") (pintype "passive"))
      (node (ref "Q6") (pin "2") (pinfunction "S_2") (pintype "passive"))
      (node (ref "Q7") (pin "2") (pinfunction "S_2") (pintype "passive"))
      (node (ref "Q8") (pin "2") (pinfunction "S_2") (pintype "passive"))
      (node (ref "R13") (pin "1") (pinfunction "1_1") (pintype "passive"))
      (node (ref "R19") (pin "1") (pinfunction "1_1") (pintype "passive"))
      (node (ref "R2") (pin "2") (pinfunction "2_2") (pintype "passive"))
      (node (ref "R25") (pin "2") (pinfunction "2_2") (pintype "passive"))
      (node (ref "R3") (pin "2") (pinfunction "2_2") (pintype "passive"))
      (node (ref "R4") (pin "2") (pinfunction "2_2") (pintype "passive"))
      (node (ref "RN1") (pin "1") (pinfunction "1_1") (pintype "passive"))
      (node (ref "RN1") (pin "2") (pinfunction "1_2") (pintype "passive"))
      (node (ref "RN1") (pin "3") (pinfunction "1_3") (pintype "passive"))
      (node (ref "RN1") (pin "4") (pinfunction "1_4") (pintype "passive"))
      (node (ref "RN4") (pin "1") (pinfunction "1_1") (pintype "passive"))
      (node (ref "RN4") (pin "2") (pinfunction "1_2") (pintype "passive"))
      (node (ref "RN4") (pin "3") (pinfunction "1_3") (pintype "passive"))
      (node (ref "RN4") (pin "4") (pinfunction "1_4") (pintype "passive"))
      (node (ref "RN6") (pin "3") (pinfunction "1_3") (pintype "passive"))
      (node (ref "RN6") (pin "7") (pinfunction "2_7") (pintype "passive"))
      (node (ref "RN6") (pin "8") (pinfunction "2_8") (pintype "passive"))
      (node (ref "TP4") (pin "1") (pinfunction "1_1") (pintype "passive"))
      (node (ref "U1") (pin "21") (pinfunction "GND_21") (pintype "power_in"))
      (node (ref "U1") (pin "3") (pinfunction "GND_3") (pintype "power_in"))
      (node (ref "U1") (pin "5") (pinfunction "GND_5") (pintype "power_in"))
      (node (ref "U2") (pin "5") (pinfunction "GND_5") (pintype "power_in"))
      (node (ref "U3") (pin "4") (pinfunction "1_4") (pintype "input"))
      (node (ref "U3") (pin "5") (pinfunction "2_5") (pintype "input"))
      (node (ref "U3") (pin "9") (pinfunction "GND_9") (pintype "power_in"))
      (node (ref "U4") (pin "2") (pinfunction "GND_2") (pintype "power_in"))
      (node (ref "U4") (pin "8") (pinfunction "STBY_8") (pintype "passive"))
      (node (ref "U5") (pin "10") (pinfunction "GND_10") (pintype "power_in"))
      (node (ref "U6") (pin "3") (pinfunction "GND_3") (pintype "power_in"))
      (node (ref "U7") (pin "3") (pinfunction "GND_3") (pintype "power_in"))
      (node (ref "X1") (pin "2") (pinfunction "GND_2") (pintype "power_in"))
      (node (ref "X1") (pin "4") (pinfunction "GND_4") (pintype "power_in"))
      (node (ref "X2") (pin "2") (pinfunction "GND_2") (pintype "power_in"))
      (node (ref "X2") (pin "4") (pinfunction "GND_4") (pintype "power_in"))
    )
    (net (code "11") (name "LED_AMS_CTRL") (class "Default")
      (node (ref "DN1") (pin "6") (pinfunction "C_6") (pintype "passive"))
      (node (ref "RN4") (pin "7") (pinfunction "2_7") (pintype "passive"))
      (node (ref "RN8") (pin "1") (pinfunction "1_1") (pintype "passive"))
      (node (ref "U1") (pin "30") (pinfunction "0_30") (pintype "bidirectional"))
    )
    (net (code "12") (name "LED_IMD_CTRL") (class "Default")
      (node (ref "DN1") (pin "4") (pinfunction "C_4") (pintype "passive"))
      (node (ref "RN1") (pin "8") (pinfunction "2_8") (pintype "passive"))
      (node (ref "RN2") (pin "4") (pinfunction "1_4") (pintype "passive"))
      (node (ref "U1") (pin "31") (pinfunction "1_31") (pintype "bidirectional"))
    )
    (net (code "13") (name "LED_MC_ERR_CTRL") (class "Default")
      (node (ref "DN1") (pin "3") (pinfunction "C_3") (pintype "passive"))
      (node (ref "RN1") (pin "6") (pinfunction "2_6") (pintype "passive"))
      (node (ref "RN2") (pin "1") (pinfunction "1_1") (pintype "passive"))
      (node (ref "U1") (pin "1") (pinfunction "3(PWM)_1") (pintype "bidirectional"))
    )
    (net (code "14") (name "LED_MODE_CTRL") (class "Default")
      (node (ref "DN1") (pin "5") (pinfunction "C_5") (pintype "passive"))
      (node (ref "RN1") (pin "7") (pinfunction "2_7") (pintype "passive"))
      (node (ref "RN2") (pin "3") (pinfunction "1_3") (pintype "passive"))
      (node (ref "U1") (pin "32") (pinfunction "2_32") (pintype "bidirectional"))
    )
    (net (code "15") (name "LED_START_CTRL") (class "Default")
      (node (ref "DN1") (pin "1") (pinfunction "C_1") (pintype "passive"))
      (node (ref "RN1") (pin "5") (pinfunction "2_5") (pintype "passive"))
      (node (ref "RN2") (pin "2") (pinfunction "1_2") (pintype "passive"))
      (node (ref "U1") (pin "2") (pinfunction "4_2") (pintype "bidirectional"))
    )
    (net (code "16") (name "Net-(A1-TRIM)") (class "Default")
      (node (ref "A1") (pin "6") (pinfunction "TRIM_6") (pintype "passive"))
      (node (ref "R19") (pin "2") (pinfunction "2_2") (pintype "passive"))
    )
    (net (code "17") (name "Net-(C13-Pad1)") (class "Default")
      (node (ref "C13") (pin "1") (pinfunction "1_1") (pintype "passive"))
      (node (ref "R18") (pin "1") (pinfunction "1_1") (pintype "passive"))
      (node (ref "R20") (pin "1") (pinfunction "1_1") (pintype "passive"))
    )
    (net (code "18") (name "Net-(D1-PadC)") (class "Default")
      (node (ref "D1") (pin "C") (pinfunction "C_C") (pintype "passive"))
      (node (ref "R23") (pin "1") (pinfunction "1_1") (pintype "passive"))
    )
    (net (code "19") (name "Net-(D2-PadC)") (class "Default")
      (node (ref "D2") (pin "C") (pinfunction "C_C") (pintype "passive"))
      (node (ref "R17") (pin "1") (pinfunction "1_1") (pintype "passive"))
    )
    (net (code "20") (name "Net-(D3-PadC)") (class "Default")
      (node (ref "D3") (pin "C") (pinfunction "C_C") (pintype "passive"))
      (node (ref "R1") (pin "1") (pinfunction "1_1") (pintype "passive"))
    )
    (net (code "21") (name "Net-(D5-A)") (class "Default")
      (node (ref "D5") (pin "2") (pinfunction "A_2") (pintype "passive"))
      (node (ref "U1") (pin "23") (pinfunction "14(A0)_23") (pintype "bidirectional"))
    )
    (net (code "22") (name "Net-(D5-C)") (class "Default")
      (node (ref "D5") (pin "1") (pinfunction "C_1") (pintype "passive"))
      (node (ref "RN6") (pin "6") (pinfunction "2_6") (pintype "passive"))
    )
    (net (code "23") (name "Net-(D6-C)") (class "Default")
      (node (ref "D6") (pin "1") (pinfunction "C_1") (pintype "passive"))
      (node (ref "RN6") (pin "1") (pinfunction "1_1") (pintype "passive"))
    )
    (net (code "24") (name "Net-(D7-C)") (class "Default")
      (node (ref "D7") (pin "1") (pinfunction "C_1") (pintype "passive"))
      (node (ref "RN6") (pin "2") (pinfunction "1_2") (pintype "passive"))
    )
    (net (code "25") (name "Net-(D100-PadC)") (class "Default")
      (node (ref "D100") (pin "C") (pinfunction "C_C") (pintype "passive"))
      (node (ref "R16") (pin "1") (pinfunction "1_1") (pintype "passive"))
    )
    (net (code "26") (name "Net-(D101-A)") (class "Default")
      (node (ref "D101") (pin "7") (pinfunction "A_7") (pintype "input"))
      (node (ref "RN7") (pin "8") (pinfunction "2_8") (pintype "passive"))
    )
    (net (code "27") (name "Net-(D101-B)") (class "Default")
      (node (ref "D101") (pin "6") (pinfunction "B_6") (pintype "input"))
      (node (ref "RN7") (pin "7") (pinfunction "2_7") (pintype "passive"))
    )
    (net (code "28") (name "Net-(D101-C)") (class "Default")
      (node (ref "D101") (pin "4") (pinfunction "C_4") (pintype "input"))
      (node (ref "RN7") (pin "6") (pinfunction "2_6") (pintype "passive"))
    )
    (net (code "29") (name "Net-(D101-D)") (class "Default")
      (node (ref "D101") (pin "2") (pinfunction "D_2") (pintype "input"))
      (node (ref "RN7") (pin "5") (pinfunction "2_5") (pintype "passive"))
    )
    (net (code "30") (name "Net-(D101-E)") (class "Default")
      (node (ref "D101") (pin "1") (pinfunction "E_1") (pintype "input"))
      (node (ref "RN5") (pin "8") (pinfunction "2_8") (pintype "passive"))
    )
    (net (code "31") (name "Net-(D101-F)") (class "Default")
      (node (ref "D101") (pin "9") (pinfunction "F_9") (pintype "input"))
      (node (ref "RN5") (pin "7") (pinfunction "2_7") (pintype "passive"))
    )
    (net (code "32") (name "Net-(D101-G)") (class "Default")
      (node (ref "D101") (pin "10") (pinfunction "G_10") (pintype "input"))
      (node (ref "RN5") (pin "6") (pinfunction "2_6") (pintype "passive"))
    )
    (net (code "33") (name "Net-(D104-PadC)") (class "Default")
      (node (ref "D104") (pin "C") (pinfunction "C_C") (pintype "passive"))
      (node (ref "R12") (pin "1") (pinfunction "1_1") (pintype "passive"))
    )
    (net (code "34") (name "Net-(D105-PadC)") (class "Default")
      (node (ref "D105") (pin "C") (pinfunction "C_C") (pintype "passive"))
      (node (ref "R8") (pin "1") (pinfunction "1_1") (pintype "passive"))
    )
    (net (code "35") (name "Net-(D106-PadC)") (class "Default")
      (node (ref "D106") (pin "C") (pinfunction "C_C") (pintype "passive"))
      (node (ref "R14") (pin "1") (pinfunction "1_1") (pintype "passive"))
    )
    (net (code "36") (name "Net-(D107-PadC)") (class "Default")
      (node (ref "D107") (pin "C") (pinfunction "C_C") (pintype "passive"))
      (node (ref "R22") (pin "1") (pinfunction "1_1") (pintype "passive"))
    )
    (net (code "37") (name "Net-(DN2A-C)") (class "Default")
      (node (ref "DN2") (pin "1") (pinfunction "C_1") (pintype "passive"))
      (node (ref "RN4") (pin "8") (pinfunction "2_8") (pintype "passive"))
      (node (ref "RN8") (pin "2") (pinfunction "1_2") (pintype "passive"))
      (node (ref "U6") (pin "4") (pinfunction "~{IN}_4") (pintype "output"))
    )
    (net (code "38") (name "Net-(DN2C-C)") (class "Default")
      (node (ref "DN2") (pin "4") (pinfunction "C_4") (pintype "passive"))
      (node (ref "RN4") (pin "5") (pinfunction "2_5") (pintype "passive"))
      (node (ref "RN8") (pin "4") (pinfunction "1_4") (pintype "passive"))
      (node (ref "U7") (pin "4") (pinfunction "~{IN}_4") (pintype "output"))
    )
    (net (code "39") (name "Net-(J1-CIPO)") (class "Default")
      (node (ref "J1") (pin "9") (pinfunction "CIPO_9") (pintype "bidirectional"))
      (node (ref "U1") (pin "16") (pinfunction "(CIPO)12_16") (pintype "bidirectional"))
      (node (ref "U3") (pin "3") (pinfunction "SDO_3") (pintype "output"))
      (node (ref "U5") (pin "17") (pinfunction "SDO_17") (pintype "output"))
    )
    (net (code "40") (name "Net-(J1-CLK)") (class "Default")
      (node (ref "J1") (pin "7") (pinfunction "CLK_7") (pintype "bidirectional"))
      (node (ref "U1") (pin "17") (pinfunction "(CLK)13_17") (pintype "bidirectional"))
      (node (ref "U3") (pin "1") (pinfunction "CLK_1") (pintype "input"))
      (node (ref "U5") (pin "14") (pinfunction "CLK_14") (pintype "input"))
    )
    (net (code "41") (name "Net-(J1-COPI)") (class "Default")
      (node (ref "J1") (pin "1") (pinfunction "COPI_1") (pintype "bidirectional"))
      (node (ref "U1") (pin "15") (pinfunction "(PWM/COPI)11_15") (pintype "bidirectional"))
      (node (ref "U3") (pin "2") (pinfunction "SDI_2") (pintype "input"))
      (node (ref "U5") (pin "16") (pinfunction "SDI_16") (pintype "input"))
    )
    (net (code "42") (name "Net-(J4-Pad1)") (class "Default")
      (node (ref "J4") (pin "1") (pinfunction "1_1") (pintype "passive"))
      (node (ref "XF1") (pin "1") (pinfunction "1_1") (pintype "passive"))
      (node (ref "XF1") (pin "2") (pinfunction "1_2") (pintype "passive"))
    )
    (net (code "43") (name "Net-(J5-Pad1)") (class "Default")
      (node (ref "J5") (pin "1") (pinfunction "1_1") (pintype "passive"))
      (node (ref "R20") (pin "2") (pinfunction "2_2") (pintype "passive"))
    )
    (net (code "44") (name "Net-(LS100-FEEDBACK)") (class "Default")
      (node (ref "LS100") (pin "F") (pinfunction "FEEDBACK_F") (pintype "bidirectional"))
      (node (ref "R15") (pin "2") (pinfunction "2_2") (pintype "passive"))
    )
    (net (code "45") (name "Net-(LS100-GND)") (class "Default")
      (node (ref "LS100") (pin "G") (pinfunction "GND_G") (pintype "power_in"))
      (node (ref "R10") (pin "1") (pinfunction "1_1") (pintype "passive"))
      (node (ref "U2") (pin "6") (pinfunction "HORNB_6") (pintype "output"))
    )
    (net (code "46") (name "Net-(LS100-MAIN)") (class "Default")
      (node (ref "C3") (pin "1") (pinfunction "1_1") (pintype "passive"))
      (node (ref "LS100") (pin "M") (pinfunction "MAIN_M") (pintype "power_in"))
      (node (ref "U2") (pin "7") (pinfunction "HORNS_7") (pintype "output"))
    )
    (net (code "47") (name "Net-(Q1-D)") (class "Default")
      (node (ref "Q1") (pin "3") (pinfunction "D_3") (pintype "passive"))
      (node (ref "R1") (pin "2") (pinfunction "2_2") (pintype "passive"))
    )
    (net (code "48") (name "Net-(Q1-G)") (class "Default")
      (node (ref "Q1") (pin "1") (pinfunction "G_1") (pintype "passive"))
      (node (ref "RN2") (pin "8") (pinfunction "2_8") (pintype "passive"))
    )
    (net (code "49") (name "Net-(Q2-D)") (class "Default")
      (node (ref "Q2") (pin "3") (pinfunction "D_3") (pintype "passive"))
      (node (ref "R8") (pin "2") (pinfunction "2_2") (pintype "passive"))
    )
    (net (code "50") (name "Net-(Q2-G)") (class "Default")
      (node (ref "Q2") (pin "1") (pinfunction "G_1") (pintype "passive"))
      (node (ref "RN2") (pin "7") (pinfunction "2_7") (pintype "passive"))
    )
    (net (code "51") (name "Net-(Q3-D)") (class "Default")
      (node (ref "Q3") (pin "3") (pinfunction "D_3") (pintype "passive"))
      (node (ref "R12") (pin "2") (pinfunction "2_2") (pintype "passive"))
    )
    (net (code "52") (name "Net-(Q3-G)") (class "Default")
      (node (ref "Q3") (pin "1") (pinfunction "G_1") (pintype "passive"))
      (node (ref "RN2") (pin "6") (pinfunction "2_6") (pintype "passive"))
    )
    (net (code "53") (name "Net-(Q4-D)") (class "Default")
      (node (ref "Q4") (pin "3") (pinfunction "D_3") (pintype "passive"))
      (node (ref "R16") (pin "2") (pinfunction "2_2") (pintype "passive"))
    )
    (net (code "54") (name "Net-(Q4-G)") (class "Default")
      (node (ref "Q4") (pin "1") (pinfunction "G_1") (pintype "passive"))
      (node (ref "RN2") (pin "5") (pinfunction "2_5") (pintype "passive"))
    )
    (net (code "55") (name "Net-(Q5-D)") (class "Default")
      (node (ref "Q5") (pin "3") (pinfunction "D_3") (pintype "passive"))
      (node (ref "R17") (pin "2") (pinfunction "2_2") (pintype "passive"))
    )
    (net (code "56") (name "Net-(Q5-G)") (class "Default")
      (node (ref "Q5") (pin "1") (pinfunction "G_1") (pintype "passive"))
      (node (ref "RN8") (pin "7") (pinfunction "2_7") (pintype "passive"))
    )
    (net (code "57") (name "Net-(Q6-D)") (class "Default")
      (node (ref "Q6") (pin "3") (pinfunction "D_3") (pintype "passive"))
      (node (ref "R22") (pin "2") (pinfunction "2_2") (pintype "passive"))
    )
    (net (code "58") (name "Net-(Q6-G)") (class "Default")
      (node (ref "Q6") (pin "1") (pinfunction "G_1") (pintype "passive"))
      (node (ref "RN8") (pin "8") (pinfunction "2_8") (pintype "passive"))
    )
    (net (code "59") (name "Net-(Q7-D)") (class "Default")
      (node (ref "Q7") (pin "3") (pinfunction "D_3") (pintype "passive"))
      (node (ref "R14") (pin "2") (pinfunction "2_2") (pintype "passive"))
    )
    (net (code "60") (name "Net-(Q7-G)") (class "Default")
      (node (ref "Q7") (pin "1") (pinfunction "G_1") (pintype "passive"))
      (node (ref "RN8") (pin "6") (pinfunction "2_6") (pintype "passive"))
    )
    (net (code "61") (name "Net-(Q8-D)") (class "Default")
      (node (ref "Q8") (pin "3") (pinfunction "D_3") (pintype "passive"))
      (node (ref "R23") (pin "2") (pinfunction "2_2") (pintype "passive"))
    )
    (net (code "62") (name "Net-(Q8-G)") (class "Default")
      (node (ref "Q8") (pin "1") (pinfunction "G_1") (pintype "passive"))
      (node (ref "RN8") (pin "5") (pinfunction "2_5") (pintype "passive"))
    )
    (net (code "63") (name "Net-(RN5B-1)") (class "Default")
      (node (ref "RN5") (pin "2") (pinfunction "1_2") (pintype "passive"))
      (node (ref "U3") (pin "17") (pinfunction "GPA5_17") (pintype "bidirectional"))
    )
    (net (code "64") (name "Net-(RN5C-1)") (class "Default")
      (node (ref "RN5") (pin "3") (pinfunction "1_3") (pintype "passive"))
      (node (ref "U3") (pin "18") (pinfunction "GPA6_18") (pintype "bidirectional"))
    )
    (net (code "65") (name "Net-(RN7B-1)") (class "Default")
      (node (ref "RN7") (pin "2") (pinfunction "1_2") (pintype "passive"))
      (node (ref "U3") (pin "13") (pinfunction "GPA1_13") (pintype "bidirectional"))
    )
    (net (code "66") (name "Net-(RN7C-1)") (class "Default")
      (node (ref "RN7") (pin "3") (pinfunction "1_3") (pintype "passive"))
      (node (ref "U3") (pin "14") (pinfunction "GPA2_14") (pintype "bidirectional"))
    )
    (net (code "67") (name "Net-(RN7D-1)") (class "Default")
      (node (ref "RN7") (pin "4") (pinfunction "1_4") (pintype "passive"))
      (node (ref "U3") (pin "15") (pinfunction "GPA3_15") (pintype "bidirectional"))
    )
    (net (code "68") (name "Net-(U1-(PWM{slash}CS)10)") (class "Default")
      (node (ref "U1") (pin "14") (pinfunction "(PWM/CS)10_14") (pintype "bidirectional"))
      (node (ref "U5") (pin "18") (pinfunction "~{CS}_18") (pintype "input"))
    )
    (net (code "69") (name "Net-(U1-(XTAL1)14)") (class "Default")
      (node (ref "C2") (pin "1") (pinfunction "1_1") (pintype "passive"))
      (node (ref "U1") (pin "7") (pinfunction "(XTAL1)14_7") (pintype "bidirectional"))
      (node (ref "X1") (pin "1") (pinfunction "1_1") (pintype "passive"))
    )
    (net (code "70") (name "Net-(U1-(XTAL2)15)") (class "Default")
      (node (ref "C1") (pin "1") (pinfunction "1_1") (pintype "passive"))
      (node (ref "U1") (pin "8") (pinfunction "(XTAL2)15_8") (pintype "bidirectional"))
      (node (ref "X1") (pin "3") (pinfunction "3_3") (pintype "passive"))
    )
    (net (code "71") (name "Net-(U1-8)") (class "Default")
      (node (ref "R9") (pin "1") (pinfunction "1_1") (pintype "passive"))
      (node (ref "U1") (pin "12") (pinfunction "8_12") (pintype "bidirectional"))
    )
    (net (code "72") (name "Net-(U1-AREF)") (class "Default")
      (node (ref "C7") (pin "1") (pinfunction "1_1") (pintype "passive"))
      (node (ref "U1") (pin "20") (pinfunction "AREF_20") (pintype "input"))
    )
    (net (code "73") (name "Net-(U1-AVDD)") (class "Default")
      (node (ref "C6") (pin "1") (pinfunction "1_1") (pintype "passive"))
      (node (ref "L1") (pin "1") (pinfunction "1_1") (pintype "passive"))
      (node (ref "U1") (pin "18") (pinfunction "AVDD_18") (pintype "power_in"))
    )
    (net (code "74") (name "Net-(U2-FEED)") (class "Default")
      (node (ref "C3") (pin "2") (pinfunction "2_2") (pintype "passive"))
      (node (ref "R10") (pin "2") (pinfunction "2_2") (pintype "passive"))
      (node (ref "R15") (pin "1") (pinfunction "1_1") (pintype "passive"))
      (node (ref "U2") (pin "4") (pinfunction "FEED_4") (pintype "input"))
    )
    (net (code "75") (name "Net-(U3-GPA0)") (class "Default")
      (node (ref "RN7") (pin "1") (pinfunction "1_1") (pintype "passive"))
      (node (ref "U3") (pin "12") (pinfunction "GPA0_12") (pintype "bidirectional"))
    )
    (net (code "76") (name "Net-(U3-GPA4)") (class "Default")
      (node (ref "RN5") (pin "1") (pinfunction "1_1") (pintype "passive"))
      (node (ref "U3") (pin "16") (pinfunction "GPA4_16") (pintype "bidirectional"))
    )
    (net (code "77") (name "Net-(U3-~{CS})") (class "Default")
      (node (ref "R9") (pin "2") (pinfunction "2_2") (pintype "passive"))
      (node (ref "U3") (pin "7") (pinfunction "~{CS}_7") (pintype "input"))
    )
    (net (code "78") (name "Net-(U4-RXD)") (class "Default")
      (node (ref "J5") (pin "2") (pinfunction "2_2") (pintype "passive"))
      (node (ref "U4") (pin "4") (pinfunction "RXD_4") (pintype "output"))
      (node (ref "U5") (pin "2") (pinfunction "RX_2") (pintype "input"))
    )
    (net (code "79") (name "Net-(U4-TXD)") (class "Default")
      (node (ref "R18") (pin "2") (pinfunction "2_2") (pintype "passive"))
      (node (ref "U4") (pin "1") (pinfunction "TXD_1") (pintype "input"))
      (node (ref "U5") (pin "1") (pinfunction "TX_1") (pintype "output"))
    )
    (net (code "80") (name "Net-(U5-OSC1)") (class "Default")
      (node (ref "C18") (pin "1") (pinfunction "1_1") (pintype "passive"))
      (node (ref "U5") (pin "9") (pinfunction "OSC1_9") (pintype "bidirectional"))
      (node (ref "X2") (pin "1") (pinfunction "1_1") (pintype "passive"))
    )
    (net (code "81") (name "Net-(U5-OSC2)") (class "Default")
      (node (ref "C19") (pin "1") (pinfunction "1_1") (pintype "passive"))
      (node (ref "U5") (pin "8") (pinfunction "OSC2_8") (pintype "bidirectional"))
      (node (ref "X2") (pin "3") (pinfunction "3_3") (pintype "passive"))
    )
    (net (code "82") (name "Net-(U5-~{RESET})") (class "Default")
      (node (ref "R21") (pin "2") (pinfunction "2_2") (pintype "passive"))
      (node (ref "U5") (pin "19") (pinfunction "~{RESET}_19") (pintype "input"))
    )
    (net (code "83") (name "RESET") (class "Default")
      (node (ref "J1") (pin "5") (pinfunction "RESET_5") (pintype "output"))
      (node (ref "R11") (pin "2") (pinfunction "2_2") (pintype "passive"))
      (node (ref "U1") (pin "29") (pinfunction "22(~{RESET})_29") (pintype "bidirectional"))
    )
    (net (code "84") (name "SHUTDOWN_F") (class "Default")
      (node (ref "J4") (pin "7") (pinfunction "7_7") (pintype "passive"))
      (node (ref "R5") (pin "1") (pinfunction "1_1") (pintype "passive"))
      (node (ref "TP1") (pin "1") (pinfunction "1_1") (pintype "passive"))
    )
    (net (code "85") (name "SHUTDOWN_F_READ") (class "Default")
      (node (ref "DN2") (pin "3") (pinfunction "C_3") (pintype "passive"))
      (node (ref "R2") (pin "1") (pinfunction "1_1") (pintype "passive"))
      (node (ref "R5") (pin "2") (pinfunction "2_2") (pintype "passive"))
      (node (ref "RN4") (pin "6") (pinfunction "2_6") (pintype "passive"))
      (node (ref "RN8") (pin "3") (pinfunction "1_3") (pintype "passive"))
      (node (ref "U1") (pin "19") (pinfunction "A6_19") (pintype "bidirectional"))
    )
    (net (code "86") (name "SHUTDOWN_G") (class "Default")
      (node (ref "J4") (pin "6") (pinfunction "6_6") (pintype "passive"))
      (node (ref "R6") (pin "1") (pinfunction "1_1") (pintype "passive"))
      (node (ref "TP5") (pin "1") (pinfunction "1_1") (pintype "passive"))
    )
    (net (code "87") (name "SHUTDOWN_G_READ") (class "Default")
      (node (ref "R3") (pin "1") (pinfunction "1_1") (pintype "passive"))
      (node (ref "R6") (pin "2") (pinfunction "2_2") (pintype "passive"))
      (node (ref "U1") (pin "24") (pinfunction "15(A1)_24") (pintype "bidirectional"))
      (node (ref "U6") (pin "2") (pinfunction "IN_2") (pintype "input"))
    )
    (net (code "88") (name "SHUTDOWN_H") (class "Default")
      (node (ref "J4") (pin "5") (pinfunction "5_5") (pintype "passive"))
      (node (ref "R7") (pin "1") (pinfunction "1_1") (pintype "passive"))
      (node (ref "TP6") (pin "1") (pinfunction "1_1") (pintype "passive"))
    )
    (net (code "89") (name "SHUTDOWN_H_READ") (class "Default")
      (node (ref "R4") (pin "1") (pinfunction "1_1") (pintype "passive"))
      (node (ref "R7") (pin "2") (pinfunction "2_2") (pintype "passive"))
      (node (ref "U1") (pin "22") (pinfunction "A7_22") (pintype "bidirectional"))
    )
    (net (code "90") (name "SHUTDOWN_I") (class "Default")
      (node (ref "J4") (pin "2") (pinfunction "2_2") (pintype "passive"))
      (node (ref "R24") (pin "1") (pinfunction "1_1") (pintype "passive"))
      (node (ref "TP7") (pin "1") (pinfunction "1_1") (pintype "passive"))
    )
    (net (code "91") (name "SHUTDOWN_I_READ") (class "Default")
      (node (ref "R24") (pin "2") (pinfunction "2_2") (pintype "passive"))
      (node (ref "R25") (pin "1") (pinfunction "1_1") (pintype "passive"))
      (node (ref "U1") (pin "9") (pinfunction "5(PWM)_9") (pintype "bidirectional"))
      (node (ref "U7") (pin "2") (pinfunction "IN_2") (pintype "input"))
    )
    (net (code "92") (name "VDD") (class "Default")
      (node (ref "A1") (pin "4") (pinfunction "OUT_4") (pintype "power_in"))
      (node (ref "C10") (pin "1") (pinfunction "1_1") (pintype "passive"))
      (node (ref "C11") (pin "1") (pinfunction "1_1") (pintype "passive"))
      (node (ref "C12") (pin "1") (pinfunction "1_1") (pintype "passive"))
      (node (ref "C14") (pin "1") (pinfunction "1_1") (pintype "passive"))
      (node (ref "C15") (pin "1") (pinfunction "1_1") (pintype "passive"))
      (node (ref "C16") (pin "1") (pinfunction "1_1") (pintype "passive"))
      (node (ref "C17") (pin "1") (pinfunction "1_1") (pintype "passive"))
      (node (ref "C4") (pin "1") (pinfunction "1_1") (pintype "passive"))
      (node (ref "C8") (pin "1") (pinfunction "1_1") (pintype "passive"))
      (node (ref "C9") (pin "1") (pinfunction "1_1") (pintype "passive"))
      (node (ref "D1") (pin "A") (pinfunction "A_A") (pintype "passive"))
      (node (ref "D100") (pin "A") (pinfunction "A_A") (pintype "passive"))
      (node (ref "D101") (pin "3") (pinfunction "VDD_3") (pintype "power_in"))
      (node (ref "D101") (pin "8") (pinfunction "VDD_8") (pintype "power_in"))
      (node (ref "D104") (pin "A") (pinfunction "A_A") (pintype "passive"))
      (node (ref "D105") (pin "A") (pinfunction "A_A") (pintype "passive"))
      (node (ref "D106") (pin "A") (pinfunction "A_A") (pintype "passive"))
      (node (ref "D107") (pin "A") (pinfunction "A_A") (pintype "passive"))
      (node (ref "D2") (pin "A") (pinfunction "A_A") (pintype "passive"))
      (node (ref "D3") (pin "A") (pinfunction "A_A") (pintype "passive"))
      (node (ref "D6") (pin "2") (pinfunction "A_2") (pintype "passive"))
      (node (ref "J1") (pin "2") (pinfunction "+5V_2") (pintype "power_in"))
      (node (ref "L1") (pin "2") (pinfunction "2_2") (pintype "passive"))
      (node (ref "R11") (pin "1") (pinfunction "1_1") (pintype "passive"))
      (node (ref "R21") (pin "1") (pinfunction "1_1") (pintype "passive"))
      (node (ref "TP3") (pin "1") (pinfunction "1_1") (pintype "passive"))
      (node (ref "U1") (pin "4") (pinfunction "VDD_4") (pintype "power_in"))
      (node (ref "U1") (pin "6") (pinfunction "VDD_6") (pintype "power_in"))
      (node (ref "U3") (pin "20") (pinfunction "VDD_20") (pintype "power_in"))
      (node (ref "U3") (pin "6") (pinfunction "~{RESET}_6") (pintype "input"))
      (node (ref "U4") (pin "3") (pinfunction "VDD_3") (pintype "power_in"))
      (node (ref "U4") (pin "5") (pinfunction "VIO_5") (pintype "power_in"))
      (node (ref "U5") (pin "20") (pinfunction "VDD_20") (pintype "power_in"))
      (node (ref "U6") (pin "5") (pinfunction "VDD_5") (pintype "power_in"))
      (node (ref "U7") (pin "5") (pinfunction "VDD_5") (pintype "power_in"))
    )
    (net (code "93") (name "unconnected-(A1-EN-Pad1)") (class "Default")
      (node (ref "A1") (pin "1") (pinfunction "EN_1") (pintype "input"))
    )
    (net (code "94") (name "unconnected-(U1-19(A5)-Pad28)") (class "Default")
      (node (ref "U1") (pin "28") (pinfunction "19(A5)_28") (pintype "bidirectional"))
    )
    (net (code "95") (name "unconnected-(U3-GPA7-Pad19)") (class "Default")
      (node (ref "U3") (pin "19") (pinfunction "GPA7_19") (pintype "bidirectional"))
    )
    (net (code "96") (name "unconnected-(U3-INT-Pad8)") (class "Default")
      (node (ref "U3") (pin "8") (pinfunction "INT_8") (pintype "output"))
    )
    (net (code "97") (name "unconnected-(U5-CLKOUT-Pad3)") (class "Default")
      (node (ref "U5") (pin "3") (pinfunction "CLKOUT_3") (pintype "output"))
    )
    (net (code "98") (name "unconnected-(U5-~{INT}-Pad13)") (class "Default")
      (node (ref "U5") (pin "13") (pinfunction "~{INT}_13") (pintype "output"))
    )
    (net (code "99") (name "unconnected-(U5-~{RX0BF}-Pad12)") (class "Default")
      (node (ref "U5") (pin "12") (pinfunction "~{RX0BF}_12") (pintype "output"))
    )
    (net (code "100") (name "unconnected-(U5-~{RX1BF}-Pad11)") (class "Default")
      (node (ref "U5") (pin "11") (pinfunction "~{RX1BF}_11") (pintype "output"))
    )
    (net (code "101") (name "unconnected-(U5-~{TX0RTS}-Pad4)") (class "Default")
      (node (ref "U5") (pin "4") (pinfunction "~{TX0RTS}_4") (pintype "input"))
    )
    (net (code "102") (name "unconnected-(U5-~{TX1RTS}-Pad5)") (class "Default")
      (node (ref "U5") (pin "5") (pinfunction "~{TX1RTS}_5") (pintype "input"))
    )
    (net (code "103") (name "unconnected-(U5-~{TX2RTS}-Pad7)") (class "Default")
      (node (ref "U5") (pin "7") (pinfunction "~{TX2RTS}_7") (pintype "input"))
    )
  )
)
